# TestbedV2.net
KiCad netlist of a schematic drawn in EAGLE
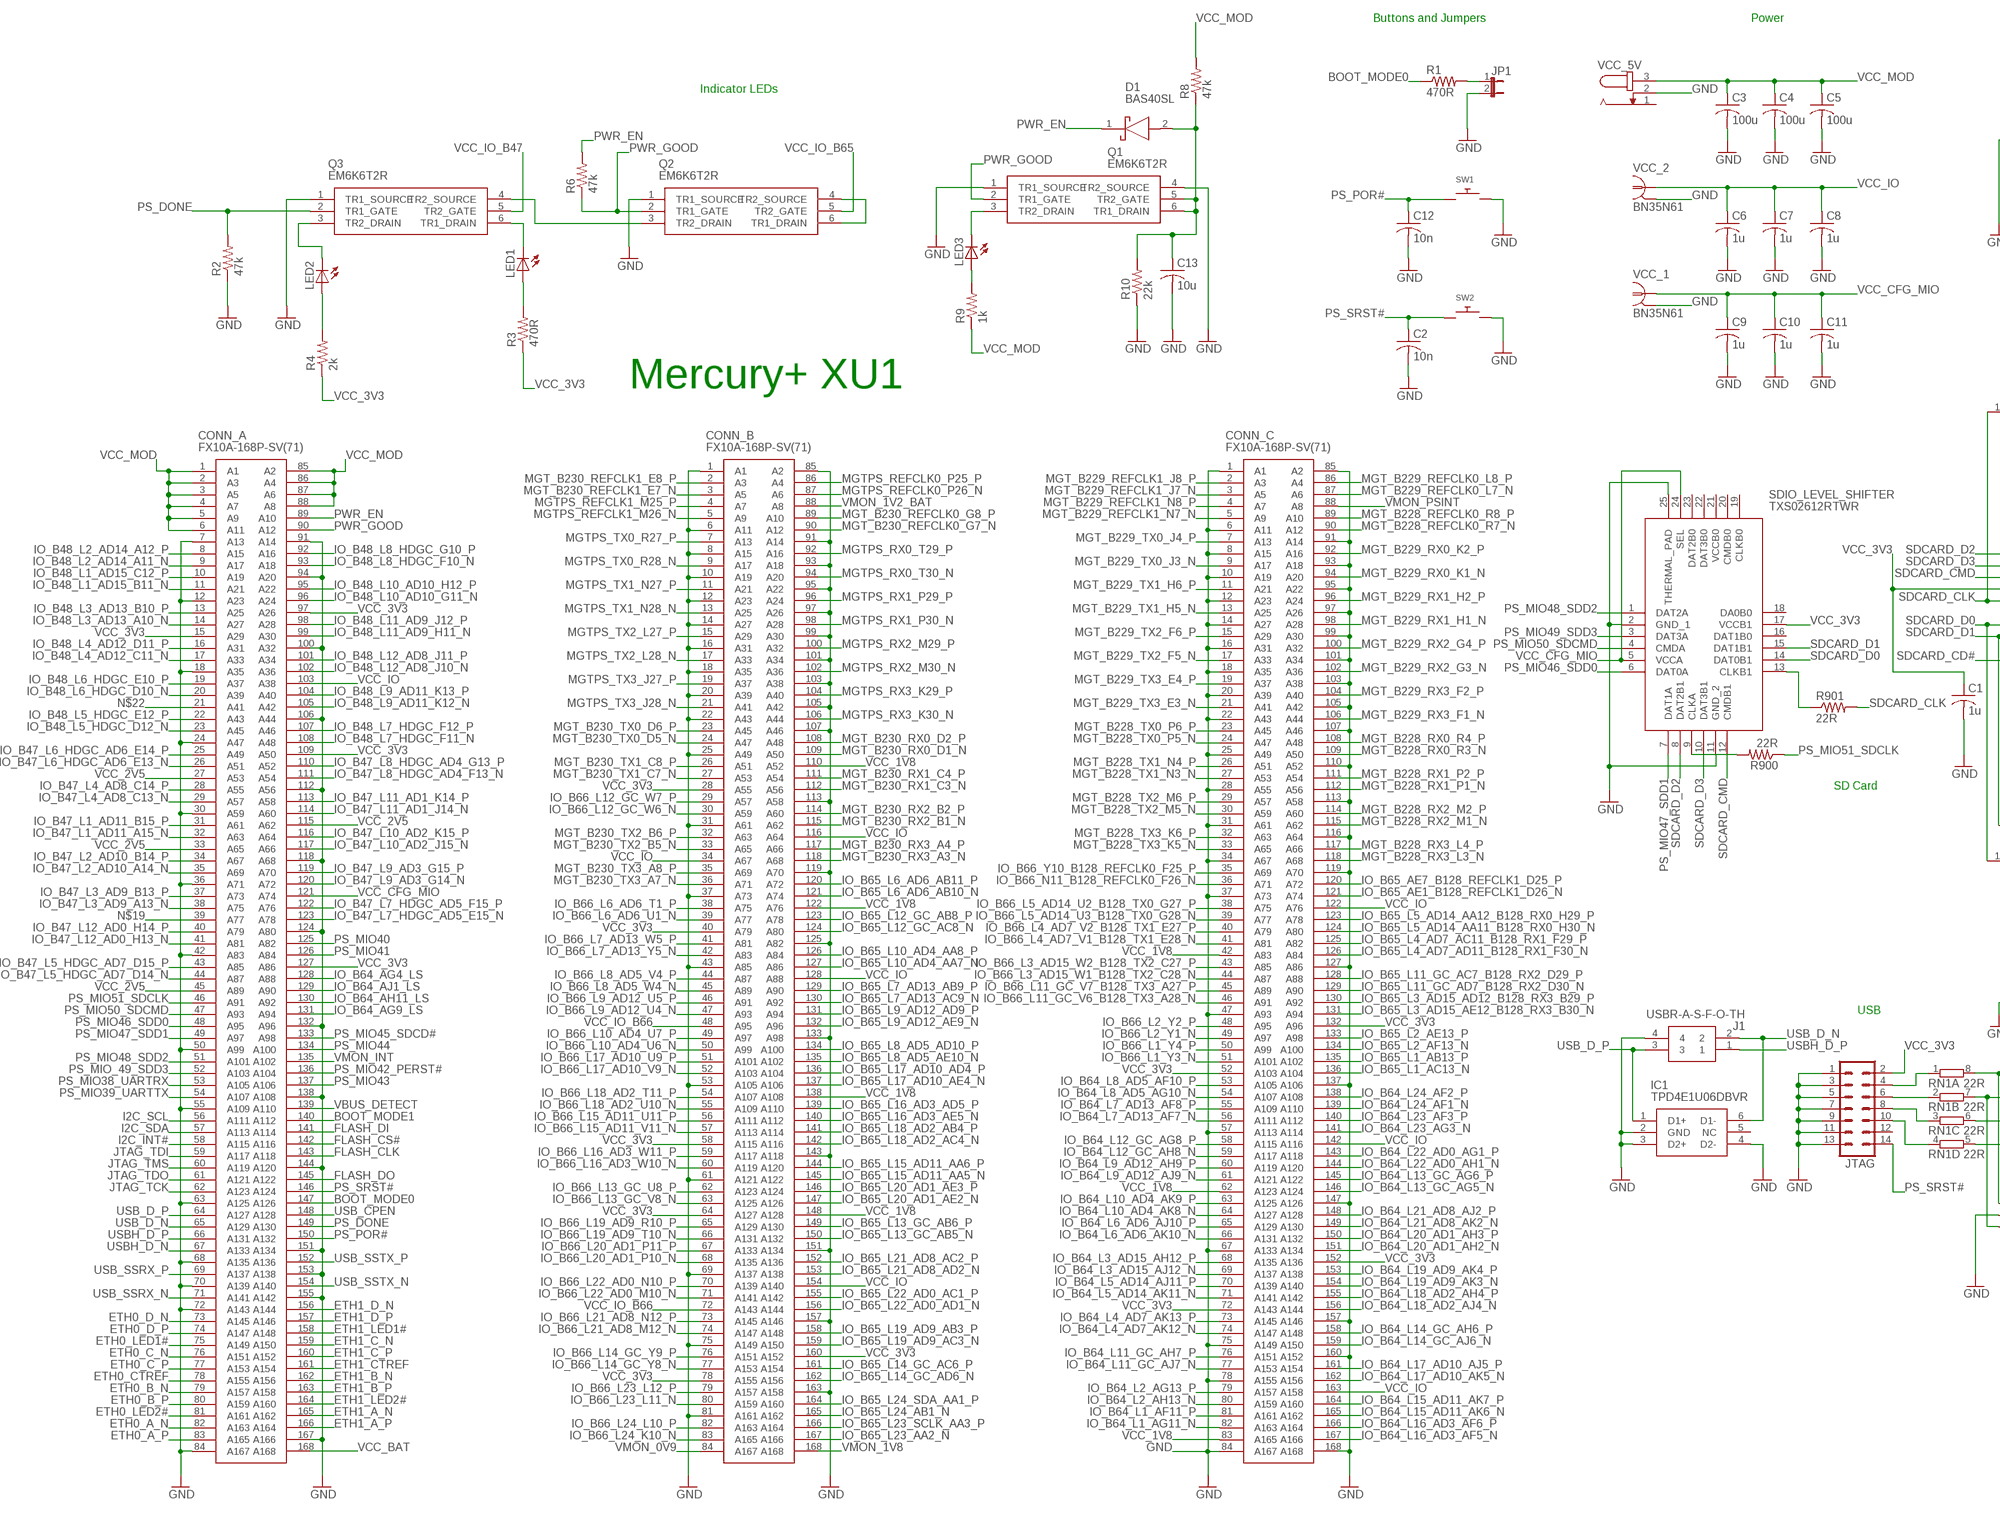
[diagram p0: schematic, sheet 1, part 1 of 2]
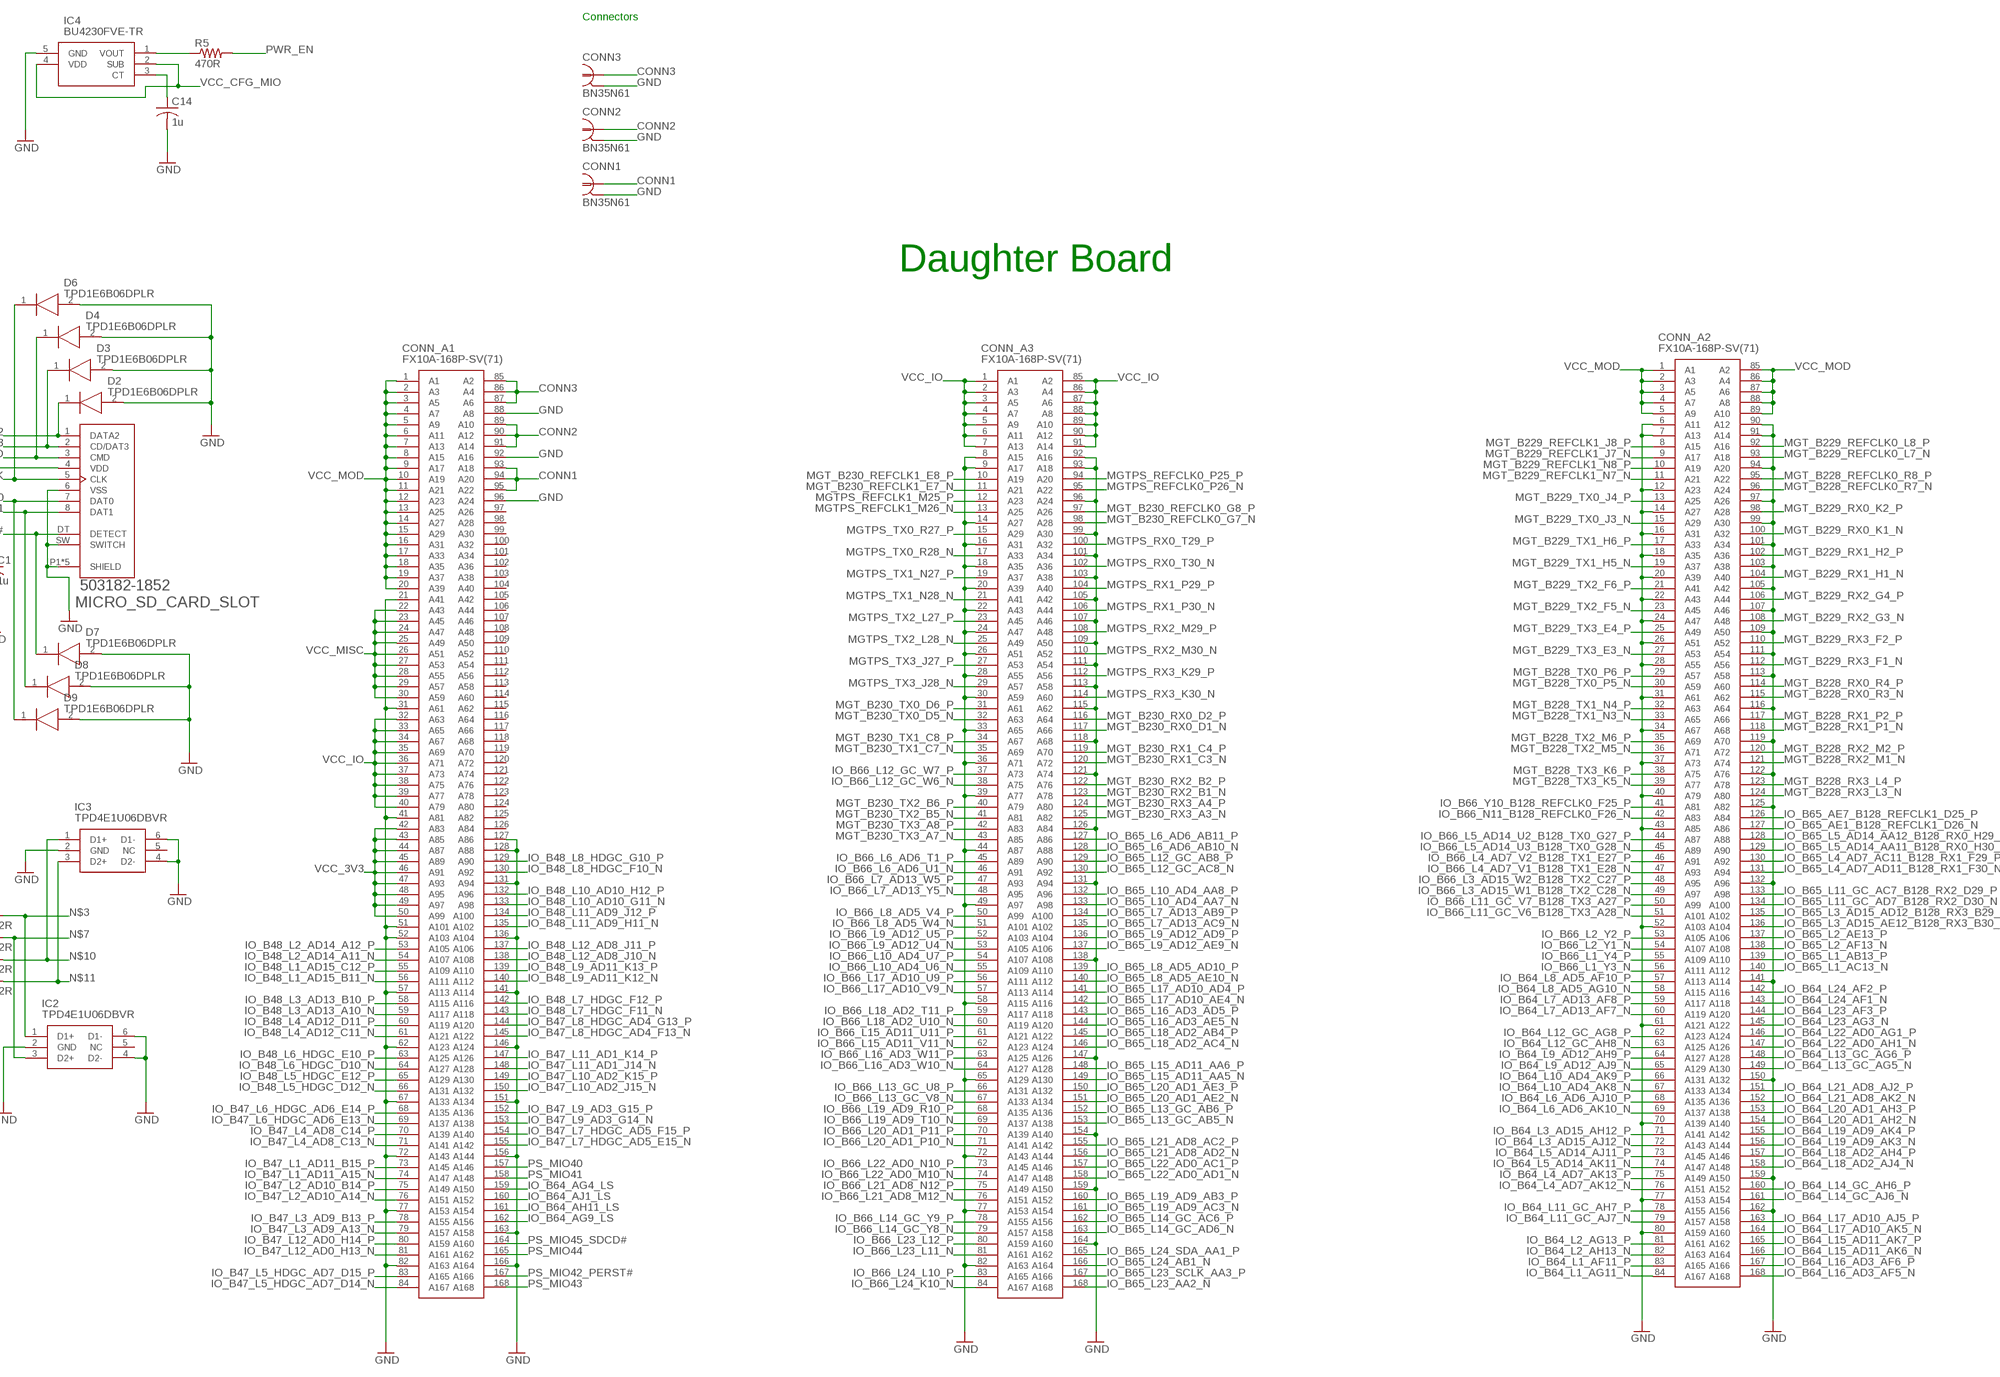
[diagram p1: schematic, sheet 1, part 2 of 2]

(export (version "E")
  (design (tool "Eeschema 10.0.6"))
  (components
    (comp (ref "C1")
      (value "1u")
      (footprint "eagle-import:C0805")
      (libsource (lib "eagle-import") (part "C-USC0805"))
    )
    (comp (ref "C2")
      (value "10n")
      (footprint "eagle-import:C0805")
      (libsource (lib "eagle-import") (part "C-USC0805"))
    )
    (comp (ref "C3")
      (value "100u")
      (footprint "eagle-import:C0805")
      (libsource (lib "eagle-import") (part "C-USC0805"))
    )
    (comp (ref "C4")
      (value "100u")
      (footprint "eagle-import:C0805")
      (libsource (lib "eagle-import") (part "C-USC0805"))
    )
    (comp (ref "C5")
      (value "100u")
      (footprint "eagle-import:C0805")
      (libsource (lib "eagle-import") (part "C-USC0805"))
    )
    (comp (ref "C6")
      (value "1u")
      (footprint "eagle-import:C0805")
      (libsource (lib "eagle-import") (part "C-USC0805"))
    )
    (comp (ref "C7")
      (value "1u")
      (footprint "eagle-import:C0805")
      (libsource (lib "eagle-import") (part "C-USC0805"))
    )
    (comp (ref "C8")
      (value "1u")
      (footprint "eagle-import:C0805")
      (libsource (lib "eagle-import") (part "C-USC0805"))
    )
    (comp (ref "C9")
      (value "1u")
      (footprint "eagle-import:C0805")
      (libsource (lib "eagle-import") (part "C-USC0805"))
    )
    (comp (ref "C10")
      (value "1u")
      (footprint "eagle-import:C0805")
      (libsource (lib "eagle-import") (part "C-USC0805"))
    )
    (comp (ref "C11")
      (value "1u")
      (footprint "eagle-import:C0805")
      (libsource (lib "eagle-import") (part "C-USC0805"))
    )
    (comp (ref "C12")
      (value "10n")
      (footprint "eagle-import:C0805")
      (libsource (lib "eagle-import") (part "C-USC0805"))
    )
    (comp (ref "C13")
      (value "10u")
      (footprint "eagle-import:C0805")
      (libsource (lib "eagle-import") (part "C-USC0805"))
    )
    (comp (ref "C14")
      (value "1u")
      (footprint "eagle-import:C0805")
      (libsource (lib "eagle-import") (part "C-USC0805"))
    )
    (comp (ref "CONN1")
      (value "BN35N61")
      (footprint "eagle-import:B35N61")
      (fields (field (name "SPICEPREFIX") "X"))
      (libsource (lib "eagle-import") (part "BN35N61"))
    )
    (comp (ref "CONN2")
      (value "BN35N61")
      (footprint "eagle-import:B35N61")
      (libsource (lib "eagle-import") (part "BN35N61"))
    )
    (comp (ref "CONN3")
      (value "BN35N61")
      (footprint "eagle-import:B35N61")
      (libsource (lib "eagle-import") (part "BN35N61"))
    )
    (comp (ref "CONN_A")
      (value "FX10A-168P-SV(71)")
      (footprint "eagle-import:FX10A-168P-SV(71)")
      (fields (field (name "MOUSER_PART_NUMBER") "798-FX10A168PSV71"))
      (libsource (lib "eagle-import") (part "FX10A-168P-SV(71)"))
    )
    (comp (ref "CONN_A1")
      (value "FX10A-168P-SV(71)")
      (footprint "eagle-import:FX10A-168P-SV(71)")
      (fields (field (name "MOUSER_PART_NUMBER") "798-FX10A168PSV71"))
      (libsource (lib "eagle-import") (part "FX10A-168P-SV(71)"))
    )
    (comp (ref "CONN_A2")
      (value "FX10A-168P-SV(71)")
      (footprint "eagle-import:FX10A-168P-SV(71)")
      (fields (field (name "MOUSER_PART_NUMBER") "798-FX10A168PSV71"))
      (libsource (lib "eagle-import") (part "FX10A-168P-SV(71)"))
    )
    (comp (ref "CONN_A3")
      (value "FX10A-168P-SV(71)")
      (footprint "eagle-import:FX10A-168P-SV(71)")
      (fields (field (name "MOUSER_PART_NUMBER") "798-FX10A168PSV71"))
      (libsource (lib "eagle-import") (part "FX10A-168P-SV(71)"))
    )
    (comp (ref "CONN_B")
      (value "FX10A-168P-SV(71)")
      (footprint "eagle-import:FX10A-168P-SV(71)")
      (fields (field (name "MOUSER_PART_NUMBER") "798-FX10A168PSV71"))
      (libsource (lib "eagle-import") (part "FX10A-168P-SV(71)"))
    )
    (comp (ref "CONN_C")
      (value "FX10A-168P-SV(71)")
      (footprint "eagle-import:FX10A-168P-SV(71)")
      (fields (field (name "MOUSER_PART_NUMBER") "798-FX10A168PSV71"))
      (libsource (lib "eagle-import") (part "FX10A-168P-SV(71)"))
    )
    (comp (ref "D1")
      (value "BAS40SL")
      (footprint "eagle-import:SODFL1006X43N")
      (fields (field (name "MOUSER_PART_NUMBER") "512-BAS40SL"))
      (libsource (lib "eagle-import") (part "BAS40SL"))
    )
    (comp (ref "D2")
      (value "TPD1E6B06DPLR")
      (footprint "eagle-import:DPL-(R-PX2SON-N2)")
      (fields (field (name "MOUSER_PART_NUMBER") "595-TPD1E6B06DPLR"))
      (libsource (lib "eagle-import") (part "TPD1E6B06DPLR"))
    )
    (comp (ref "D3")
      (value "TPD1E6B06DPLR")
      (footprint "eagle-import:DPL-(R-PX2SON-N2)")
      (fields (field (name "MOUSER_PART_NUMBER") "595-TPD1E6B06DPLR"))
      (libsource (lib "eagle-import") (part "TPD1E6B06DPLR"))
    )
    (comp (ref "D4")
      (value "TPD1E6B06DPLR")
      (footprint "eagle-import:DPL-(R-PX2SON-N2)")
      (fields (field (name "MOUSER_PART_NUMBER") "595-TPD1E6B06DPLR"))
      (libsource (lib "eagle-import") (part "TPD1E6B06DPLR"))
    )
    (comp (ref "D6")
      (value "TPD1E6B06DPLR")
      (footprint "eagle-import:DPL-(R-PX2SON-N2)")
      (fields (field (name "MOUSER_PART_NUMBER") "595-TPD1E6B06DPLR"))
      (libsource (lib "eagle-import") (part "TPD1E6B06DPLR"))
    )
    (comp (ref "D7")
      (value "TPD1E6B06DPLR")
      (footprint "eagle-import:DPL-(R-PX2SON-N2)")
      (fields (field (name "MOUSER_PART_NUMBER") "595-TPD1E6B06DPLR"))
      (libsource (lib "eagle-import") (part "TPD1E6B06DPLR"))
    )
    (comp (ref "D8")
      (value "TPD1E6B06DPLR")
      (footprint "eagle-import:DPL-(R-PX2SON-N2)")
      (fields (field (name "MOUSER_PART_NUMBER") "595-TPD1E6B06DPLR"))
      (libsource (lib "eagle-import") (part "TPD1E6B06DPLR"))
    )
    (comp (ref "D9")
      (value "TPD1E6B06DPLR")
      (footprint "eagle-import:DPL-(R-PX2SON-N2)")
      (fields (field (name "MOUSER_PART_NUMBER") "595-TPD1E6B06DPLR"))
      (libsource (lib "eagle-import") (part "TPD1E6B06DPLR"))
    )
    (comp (ref "IC1")
      (value "TPD4E1U06DBVR")
      (footprint "eagle-import:SOT95P280X145-6N")
      (fields (field (name "MOUSER_PART_NUMBER") "595-TPD4E1U06DBVR"))
      (libsource (lib "eagle-import") (part "TPD4E1U06DBVR"))
    )
    (comp (ref "IC2")
      (value "TPD4E1U06DBVR")
      (footprint "eagle-import:SOT95P280X145-6N")
      (fields (field (name "MOUSER_PART_NUMBER") "595-TPD4E1U06DBVR"))
      (libsource (lib "eagle-import") (part "TPD4E1U06DBVR"))
    )
    (comp (ref "IC3")
      (value "TPD4E1U06DBVR")
      (footprint "eagle-import:SOT95P280X145-6N")
      (fields (field (name "MOUSER_PART_NUMBER") "595-TPD4E1U06DBVR"))
      (libsource (lib "eagle-import") (part "TPD4E1U06DBVR"))
    )
    (comp (ref "IC4")
      (value "BU4230FVE-TR")
      (footprint "eagle-import:BU4230FVETR")
      (fields (field (name "MOUSER_PART_NUMBER") "755-BU4230FVE-TR"))
      (libsource (lib "eagle-import") (part "BU4230FVE-TR"))
    )
    (comp (ref "J1")
      (value "USBR-A-S-F-O-TH")
      (footprint "eagle-import:USBR-A-S-F-O-TH")
      (fields (field (name "MOUSER_PART_NUMBER") "200-USBRASFOTH"))
      (libsource (lib "eagle-import") (part "USBR-A-S-F-O-TH"))
    )
    (comp (ref "JP1")
      (value "JP1E")
      (footprint "eagle-import:JP1")
      (libsource (lib "eagle-import") (part "JP1E"))
    )
    (comp (ref "JTAG")
      (value "MA07-2")
      (footprint "eagle-import:MA07-2")
      (libsource (lib "eagle-import") (part "MA07-2"))
    )
    (comp (ref "LED1")
      (value "LEDCHIP-LED0805")
      (footprint "eagle-import:CHIP-LED0805")
      (libsource (lib "eagle-import") (part "LEDCHIP-LED0805"))
    )
    (comp (ref "LED2")
      (value "LEDCHIP-LED0805")
      (footprint "eagle-import:CHIP-LED0805")
      (libsource (lib "eagle-import") (part "LEDCHIP-LED0805"))
    )
    (comp (ref "LED3")
      (value "LEDCHIP-LED0805")
      (footprint "eagle-import:CHIP-LED0805")
      (libsource (lib "eagle-import") (part "LEDCHIP-LED0805"))
    )
    (comp (ref "MICRO_SD_CARD_SLOT")
      (value "503182-1852")
      (footprint "eagle-import:MOLEX_503182-1852")
      (fields
        (field (name "DIGI-KEY_PART_NUMBER") "WM12834CT-ND")
        (field (name "MF") "Molex")
        (field (name "MP") "5031821852")
      )
      (libsource (lib "eagle-import") (part "503182-1852"))
    )
    (comp (ref "Q1")
      (value "EM6K6T2R")
      (footprint "eagle-import:SOTFL50P160X55-6N")
      (fields (field (name "MOUSER_PART_NUMBER") "755-EM6K6T2R"))
      (libsource (lib "eagle-import") (part "EM6K6T2R"))
    )
    (comp (ref "Q2")
      (value "EM6K6T2R")
      (footprint "eagle-import:SOTFL50P160X55-6N")
      (fields (field (name "MOUSER_PART_NUMBER") "755-EM6K6T2R"))
      (libsource (lib "eagle-import") (part "EM6K6T2R"))
    )
    (comp (ref "Q3")
      (value "EM6K6T2R")
      (footprint "eagle-import:SOTFL50P160X55-6N")
      (fields (field (name "MOUSER_PART_NUMBER") "755-EM6K6T2R"))
      (libsource (lib "eagle-import") (part "EM6K6T2R"))
    )
    (comp (ref "R1")
      (value "470R")
      (footprint "eagle-import:R0805")
      (libsource (lib "eagle-import") (part "R-US_R0805"))
    )
    (comp (ref "R2")
      (value "47k")
      (footprint "eagle-import:R0805")
      (libsource (lib "eagle-import") (part "R-US_R0805"))
    )
    (comp (ref "R3")
      (value "470R")
      (footprint "eagle-import:R0805")
      (libsource (lib "eagle-import") (part "R-US_R0805"))
    )
    (comp (ref "R4")
      (value "2k")
      (footprint "eagle-import:R0805")
      (libsource (lib "eagle-import") (part "R-US_R0805"))
    )
    (comp (ref "R5")
      (value "470R")
      (footprint "eagle-import:R0805")
      (libsource (lib "eagle-import") (part "R-US_R0805"))
    )
    (comp (ref "R6")
      (value "47k")
      (footprint "eagle-import:R0805")
      (libsource (lib "eagle-import") (part "R-US_R0805"))
    )
    (comp (ref "R8")
      (value "47k")
      (footprint "eagle-import:R0805")
      (libsource (lib "eagle-import") (part "R-US_R0805"))
    )
    (comp (ref "R9")
      (value "1k")
      (footprint "eagle-import:R0805")
      (libsource (lib "eagle-import") (part "R-US_R0805"))
    )
    (comp (ref "R10")
      (value "22k")
      (footprint "eagle-import:R0805")
      (libsource (lib "eagle-import") (part "R-US_R0805"))
    )
    (comp (ref "R900")
      (value "22R")
      (footprint "eagle-import:R0805")
      (libsource (lib "eagle-import") (part "R-US_R0805"))
    )
    (comp (ref "R901")
      (value "22R")
      (footprint "eagle-import:R0805")
      (libsource (lib "eagle-import") (part "R-US_R0805"))
    )
    (comp (ref "RN1")
      (value "22R")
      (footprint "eagle-import:4X0402ARV341")
      (libsource (lib "eagle-import") (part "4R-N0402ARV341"))
    )
    (comp (ref "SDIO_LEVEL_SHIFTER")
      (value "TXS02612RTWR")
      (footprint "eagle-import:QFN50P400X400X80-25N")
      (fields (field (name "MOUSER_PART_NUMBER") "595-TXS02612RTWR"))
      (libsource (lib "eagle-import") (part "TXS02612RTWR"))
    )
    (comp (ref "SW1")
      (value "SWITCH_PUSHBUTTONSOFTTOUCHSMD_SJ")
      (footprint "eagle-import:PUSHBUTTON_SMD_SJ")
      (libsource (lib "eagle-import") (part "SWITCH_PUSHBUTTONSOFTTOUCHSMD_SJ"))
    )
    (comp (ref "SW2")
      (value "SWITCH_PUSHBUTTONSOFTTOUCHSMD_SJ")
      (footprint "eagle-import:PUSHBUTTON_SMD_SJ")
      (libsource (lib "eagle-import") (part "SWITCH_PUSHBUTTONSOFTTOUCHSMD_SJ"))
    )
    (comp (ref "VCC_1")
      (value "BN35N61")
      (footprint "eagle-import:B35N61")
      (libsource (lib "eagle-import") (part "BN35N61"))
    )
    (comp (ref "VCC_2")
      (value "BN35N61")
      (footprint "eagle-import:B35N61")
      (libsource (lib "eagle-import") (part "BN35N61"))
    )
    (comp (ref "VCC_5V")
      (value "JACK-PLUG1")
      (footprint "eagle-import:SPC4078")
      (libsource (lib "eagle-import") (part "JACK-PLUG1"))
    )
  )
  (nets
    (net (code "1") (name "/BOOT_MODE0") (class "Default")
      (node (ref "CONN_A") (pin "147") (pinfunction "A126_147") (pintype "bidirectional"))
      (node (ref "R1") (pin "1") (pinfunction "1_1") (pintype "passive"))
    )
    (net (code "2") (name "/BOOT_MODE1") (class "Default")
      (node (ref "CONN_A") (pin "140") (pinfunction "A112_140") (pintype "bidirectional"))
    )
    (net (code "3") (name "/CONN1") (class "Default")
      (node (ref "CONN1") (pin "1") (pinfunction "1_1") (pintype "passive"))
      (node (ref "CONN_A1") (pin "93") (pinfunction "A18_93") (pintype "bidirectional"))
      (node (ref "CONN_A1") (pin "94") (pinfunction "A20_94") (pintype "bidirectional"))
      (node (ref "CONN_A1") (pin "95") (pinfunction "A22_95") (pintype "bidirectional"))
    )
    (net (code "4") (name "/CONN2") (class "Default")
      (node (ref "CONN2") (pin "1") (pinfunction "1_1") (pintype "passive"))
      (node (ref "CONN_A1") (pin "89") (pinfunction "A10_89") (pintype "bidirectional"))
      (node (ref "CONN_A1") (pin "90") (pinfunction "A12_90") (pintype "bidirectional"))
      (node (ref "CONN_A1") (pin "91") (pinfunction "A14_91") (pintype "bidirectional"))
    )
    (net (code "5") (name "/CONN3") (class "Default")
      (node (ref "CONN3") (pin "1") (pinfunction "1_1") (pintype "passive"))
      (node (ref "CONN_A1") (pin "85") (pinfunction "A2_85") (pintype "bidirectional"))
      (node (ref "CONN_A1") (pin "86") (pinfunction "A4_86") (pintype "bidirectional"))
      (node (ref "CONN_A1") (pin "87") (pinfunction "A6_87") (pintype "bidirectional"))
    )
    (net (code "6") (name "/ETH0_A_N") (class "Default")
      (node (ref "CONN_A") (pin "82") (pinfunction "A163_82") (pintype "bidirectional"))
    )
    (net (code "7") (name "/ETH0_A_P") (class "Default")
      (node (ref "CONN_A") (pin "83") (pinfunction "A165_83") (pintype "bidirectional"))
    )
    (net (code "8") (name "/ETH0_B_N") (class "Default")
      (node (ref "CONN_A") (pin "79") (pinfunction "A157_79") (pintype "bidirectional"))
    )
    (net (code "9") (name "/ETH0_B_P") (class "Default")
      (node (ref "CONN_A") (pin "80") (pinfunction "A159_80") (pintype "bidirectional"))
    )
    (net (code "10") (name "/ETH0_CTREF") (class "Default")
      (node (ref "CONN_A") (pin "78") (pinfunction "A155_78") (pintype "bidirectional"))
    )
    (net (code "11") (name "/ETH0_C_N") (class "Default")
      (node (ref "CONN_A") (pin "76") (pinfunction "A151_76") (pintype "bidirectional"))
    )
    (net (code "12") (name "/ETH0_C_P") (class "Default")
      (node (ref "CONN_A") (pin "77") (pinfunction "A153_77") (pintype "bidirectional"))
    )
    (net (code "13") (name "/ETH0_D_N") (class "Default")
      (node (ref "CONN_A") (pin "73") (pinfunction "A145_73") (pintype "bidirectional"))
    )
    (net (code "14") (name "/ETH0_D_P") (class "Default")
      (node (ref "CONN_A") (pin "74") (pinfunction "A147_74") (pintype "bidirectional"))
    )
    (net (code "15") (name "/ETH0_LED1#") (class "Default")
      (node (ref "CONN_A") (pin "75") (pinfunction "A149_75") (pintype "bidirectional"))
    )
    (net (code "16") (name "/ETH0_LED2#") (class "Default")
      (node (ref "CONN_A") (pin "81") (pinfunction "A161_81") (pintype "bidirectional"))
    )
    (net (code "17") (name "/ETH1_A_N") (class "Default")
      (node (ref "CONN_A") (pin "165") (pinfunction "A162_165") (pintype "bidirectional"))
    )
    (net (code "18") (name "/ETH1_A_P") (class "Default")
      (node (ref "CONN_A") (pin "166") (pinfunction "A164_166") (pintype "bidirectional"))
    )
    (net (code "19") (name "/ETH1_B_N") (class "Default")
      (node (ref "CONN_A") (pin "162") (pinfunction "A156_162") (pintype "bidirectional"))
    )
    (net (code "20") (name "/ETH1_B_P") (class "Default")
      (node (ref "CONN_A") (pin "163") (pinfunction "A158_163") (pintype "bidirectional"))
    )
    (net (code "21") (name "/ETH1_CTREF") (class "Default")
      (node (ref "CONN_A") (pin "161") (pinfunction "A154_161") (pintype "bidirectional"))
    )
    (net (code "22") (name "/ETH1_C_N") (class "Default")
      (node (ref "CONN_A") (pin "159") (pinfunction "A150_159") (pintype "bidirectional"))
    )
    (net (code "23") (name "/ETH1_C_P") (class "Default")
      (node (ref "CONN_A") (pin "160") (pinfunction "A152_160") (pintype "bidirectional"))
    )
    (net (code "24") (name "/ETH1_D_N") (class "Default")
      (node (ref "CONN_A") (pin "156") (pinfunction "A144_156") (pintype "bidirectional"))
    )
    (net (code "25") (name "/ETH1_D_P") (class "Default")
      (node (ref "CONN_A") (pin "157") (pinfunction "A146_157") (pintype "bidirectional"))
    )
    (net (code "26") (name "/ETH1_LED1#") (class "Default")
      (node (ref "CONN_A") (pin "158") (pinfunction "A148_158") (pintype "bidirectional"))
    )
    (net (code "27") (name "/ETH1_LED2#") (class "Default")
      (node (ref "CONN_A") (pin "164") (pinfunction "A160_164") (pintype "bidirectional"))
    )
    (net (code "28") (name "/FLASH_CLK") (class "Default")
      (node (ref "CONN_A") (pin "143") (pinfunction "A118_143") (pintype "bidirectional"))
    )
    (net (code "29") (name "/FLASH_CS#") (class "Default")
      (node (ref "CONN_A") (pin "142") (pinfunction "A116_142") (pintype "bidirectional"))
    )
    (net (code "30") (name "/FLASH_DI") (class "Default")
      (node (ref "CONN_A") (pin "141") (pinfunction "A114_141") (pintype "bidirectional"))
    )
    (net (code "31") (name "/FLASH_DO") (class "Default")
      (node (ref "CONN_A") (pin "145") (pinfunction "A122_145") (pintype "bidirectional"))
    )
    (net (code "32") (name "/I2C_INT#") (class "Default")
      (node (ref "CONN_A") (pin "58") (pinfunction "A115_58") (pintype "bidirectional"))
    )
    (net (code "33") (name "/I2C_SCL") (class "Default")
      (node (ref "CONN_A") (pin "56") (pinfunction "A111_56") (pintype "bidirectional"))
    )
    (net (code "34") (name "/I2C_SDA") (class "Default")
      (node (ref "CONN_A") (pin "57") (pinfunction "A113_57") (pintype "bidirectional"))
    )
    (net (code "35") (name "/IO_B47_L1_AD11_A15_N") (class "Default")
      (node (ref "CONN_A") (pin "32") (pinfunction "A63_32") (pintype "bidirectional"))
      (node (ref "CONN_A1") (pin "74") (pinfunction "A147_74") (pintype "bidirectional"))
    )
    (net (code "36") (name "/IO_B47_L1_AD11_B15_P") (class "Default")
      (node (ref "CONN_A") (pin "31") (pinfunction "A61_31") (pintype "bidirectional"))
      (node (ref "CONN_A1") (pin "73") (pinfunction "A145_73") (pintype "bidirectional"))
    )
    (net (code "37") (name "/IO_B47_L2_AD10_A14_N") (class "Default")
      (node (ref "CONN_A") (pin "35") (pinfunction "A69_35") (pintype "bidirectional"))
      (node (ref "CONN_A1") (pin "76") (pinfunction "A151_76") (pintype "bidirectional"))
    )
    (net (code "38") (name "/IO_B47_L2_AD10_B14_P") (class "Default")
      (node (ref "CONN_A") (pin "34") (pinfunction "A67_34") (pintype "bidirectional"))
      (node (ref "CONN_A1") (pin "75") (pinfunction "A149_75") (pintype "bidirectional"))
    )
    (net (code "39") (name "/IO_B47_L3_AD9_A13_N") (class "Default")
      (node (ref "CONN_A") (pin "38") (pinfunction "A75_38") (pintype "bidirectional"))
      (node (ref "CONN_A1") (pin "79") (pinfunction "A157_79") (pintype "bidirectional"))
    )
    (net (code "40") (name "/IO_B47_L3_AD9_B13_P") (class "Default")
      (node (ref "CONN_A") (pin "37") (pinfunction "A73_37") (pintype "bidirectional"))
      (node (ref "CONN_A1") (pin "78") (pinfunction "A155_78") (pintype "bidirectional"))
    )
    (net (code "41") (name "/IO_B47_L4_AD8_C13_N") (class "Default")
      (node (ref "CONN_A") (pin "29") (pinfunction "A57_29") (pintype "bidirectional"))
      (node (ref "CONN_A1") (pin "71") (pinfunction "A141_71") (pintype "bidirectional"))
    )
    (net (code "42") (name "/IO_B47_L4_AD8_C14_P") (class "Default")
      (node (ref "CONN_A") (pin "28") (pinfunction "A55_28") (pintype "bidirectional"))
      (node (ref "CONN_A1") (pin "70") (pinfunction "A139_70") (pintype "bidirectional"))
    )
    (net (code "43") (name "/IO_B47_L5_HDGC_AD7_D14_N") (class "Default")
      (node (ref "CONN_A") (pin "44") (pinfunction "A87_44") (pintype "bidirectional"))
      (node (ref "CONN_A1") (pin "84") (pinfunction "A167_84") (pintype "bidirectional"))
    )
    (net (code "44") (name "/IO_B47_L5_HDGC_AD7_D15_P") (class "Default")
      (node (ref "CONN_A") (pin "43") (pinfunction "A85_43") (pintype "bidirectional"))
      (node (ref "CONN_A1") (pin "83") (pinfunction "A165_83") (pintype "bidirectional"))
    )
    (net (code "45") (name "/IO_B47_L6_HDGC_AD6_E13_N") (class "Default")
      (node (ref "CONN_A") (pin "26") (pinfunction "A51_26") (pintype "bidirectional"))
      (node (ref "CONN_A1") (pin "69") (pinfunction "A137_69") (pintype "bidirectional"))
    )
    (net (code "46") (name "/IO_B47_L6_HDGC_AD6_E14_P") (class "Default")
      (node (ref "CONN_A") (pin "25") (pinfunction "A49_25") (pintype "bidirectional"))
      (node (ref "CONN_A1") (pin "68") (pinfunction "A135_68") (pintype "bidirectional"))
    )
    (net (code "47") (name "/IO_B47_L7_HDGC_AD5_E15_N") (class "Default")
      (node (ref "CONN_A") (pin "123") (pinfunction "A78_123") (pintype "bidirectional"))
      (node (ref "CONN_A1") (pin "155") (pinfunction "A142_155") (pintype "bidirectional"))
    )
    (net (code "48") (name "/IO_B47_L7_HDGC_AD5_F15_P") (class "Default")
      (node (ref "CONN_A") (pin "122") (pinfunction "A76_122") (pintype "bidirectional"))
      (node (ref "CONN_A1") (pin "154") (pinfunction "A140_154") (pintype "bidirectional"))
    )
    (net (code "49") (name "/IO_B47_L8_HDGC_AD4_F13_N") (class "Default")
      (node (ref "CONN_A") (pin "111") (pinfunction "A54_111") (pintype "bidirectional"))
      (node (ref "CONN_A1") (pin "145") (pinfunction "A122_145") (pintype "bidirectional"))
    )
    (net (code "50") (name "/IO_B47_L8_HDGC_AD4_G13_P") (class "Default")
      (node (ref "CONN_A") (pin "110") (pinfunction "A52_110") (pintype "bidirectional"))
      (node (ref "CONN_A1") (pin "144") (pinfunction "A120_144") (pintype "bidirectional"))
    )
    (net (code "51") (name "/IO_B47_L9_AD3_G14_N") (class "Default")
      (node (ref "CONN_A") (pin "120") (pinfunction "A72_120") (pintype "bidirectional"))
      (node (ref "CONN_A1") (pin "153") (pinfunction "A138_153") (pintype "bidirectional"))
    )
    (net (code "52") (name "/IO_B47_L9_AD3_G15_P") (class "Default")
      (node (ref "CONN_A") (pin "119") (pinfunction "A70_119") (pintype "bidirectional"))
      (node (ref "CONN_A1") (pin "152") (pinfunction "A136_152") (pintype "bidirectional"))
    )
    (net (code "53") (name "/IO_B47_L10_AD2_J15_N") (class "Default")
      (node (ref "CONN_A") (pin "117") (pinfunction "A66_117") (pintype "bidirectional"))
      (node (ref "CONN_A1") (pin "150") (pinfunction "A132_150") (pintype "bidirectional"))
    )
    (net (code "54") (name "/IO_B47_L10_AD2_K15_P") (class "Default")
      (node (ref "CONN_A") (pin "116") (pinfunction "A64_116") (pintype "bidirectional"))
      (node (ref "CONN_A1") (pin "149") (pinfunction "A130_149") (pintype "bidirectional"))
    )
    (net (code "55") (name "/IO_B47_L11_AD1_J14_N") (class "Default")
      (node (ref "CONN_A") (pin "114") (pinfunction "A60_114") (pintype "bidirectional"))
      (node (ref "CONN_A1") (pin "148") (pinfunction "A128_148") (pintype "bidirectional"))
    )
    (net (code "56") (name "/IO_B47_L11_AD1_K14_P") (class "Default")
      (node (ref "CONN_A") (pin "113") (pinfunction "A58_113") (pintype "bidirectional"))
      (node (ref "CONN_A1") (pin "147") (pinfunction "A126_147") (pintype "bidirectional"))
    )
    (net (code "57") (name "/IO_B47_L12_AD0_H13_N") (class "Default")
      (node (ref "CONN_A") (pin "41") (pinfunction "A81_41") (pintype "bidirectional"))
      (node (ref "CONN_A1") (pin "81") (pinfunction "A161_81") (pintype "bidirectional"))
    )
    (net (code "58") (name "/IO_B47_L12_AD0_H14_P") (class "Default")
      (node (ref "CONN_A") (pin "40") (pinfunction "A79_40") (pintype "bidirectional"))
      (node (ref "CONN_A1") (pin "80") (pinfunction "A159_80") (pintype "bidirectional"))
    )
    (net (code "59") (name "/IO_B48_L1_AD15_B11_N") (class "Default")
      (node (ref "CONN_A") (pin "11") (pinfunction "A21_11") (pintype "bidirectional"))
      (node (ref "CONN_A1") (pin "56") (pinfunction "A111_56") (pintype "bidirectional"))
    )
    (net (code "60") (name "/IO_B48_L1_AD15_C12_P") (class "Default")
      (node (ref "CONN_A") (pin "10") (pinfunction "A19_10") (pintype "bidirectional"))
      (node (ref "CONN_A1") (pin "55") (pinfunction "A109_55") (pintype "bidirectional"))
    )
    (net (code "61") (name "/IO_B48_L2_AD14_A11_N") (class "Default")
      (node (ref "CONN_A") (pin "9") (pinfunction "A17_9") (pintype "bidirectional"))
      (node (ref "CONN_A1") (pin "54") (pinfunction "A107_54") (pintype "bidirectional"))
    )
    (net (code "62") (name "/IO_B48_L2_AD14_A12_P") (class "Default")
      (node (ref "CONN_A") (pin "8") (pinfunction "A15_8") (pintype "bidirectional"))
      (node (ref "CONN_A1") (pin "53") (pinfunction "A105_53") (pintype "bidirectional"))
    )
    (net (code "63") (name "/IO_B48_L3_AD13_A10_N") (class "Default")
      (node (ref "CONN_A") (pin "14") (pinfunction "A27_14") (pintype "bidirectional"))
      (node (ref "CONN_A1") (pin "59") (pinfunction "A117_59") (pintype "bidirectional"))
    )
    (net (code "64") (name "/IO_B48_L3_AD13_B10_P") (class "Default")
      (node (ref "CONN_A") (pin "13") (pinfunction "A25_13") (pintype "bidirectional"))
      (node (ref "CONN_A1") (pin "58") (pinfunction "A115_58") (pintype "bidirectional"))
    )
    (net (code "65") (name "/IO_B48_L4_AD12_C11_N") (class "Default")
      (node (ref "CONN_A") (pin "17") (pinfunction "A33_17") (pintype "bidirectional"))
      (node (ref "CONN_A1") (pin "61") (pinfunction "A121_61") (pintype "bidirectional"))
    )
    (net (code "66") (name "/IO_B48_L4_AD12_D11_P") (class "Default")
      (node (ref "CONN_A") (pin "16") (pinfunction "A31_16") (pintype "bidirectional"))
      (node (ref "CONN_A1") (pin "60") (pinfunction "A119_60") (pintype "bidirectional"))
    )
    (net (code "67") (name "/IO_B48_L5_HDGC_D12_N") (class "Default")
      (node (ref "CONN_A") (pin "23") (pinfunction "A45_23") (pintype "bidirectional"))
      (node (ref "CONN_A1") (pin "66") (pinfunction "A131_66") (pintype "bidirectional"))
    )
    (net (code "68") (name "/IO_B48_L5_HDGC_E12_P") (class "Default")
      (node (ref "CONN_A") (pin "22") (pinfunction "A43_22") (pintype "bidirectional"))
      (node (ref "CONN_A1") (pin "65") (pinfunction "A129_65") (pintype "bidirectional"))
    )
    (net (code "69") (name "/IO_B48_L6_HDGC_D10_N") (class "Default")
      (node (ref "CONN_A") (pin "20") (pinfunction "A39_20") (pintype "bidirectional"))
      (node (ref "CONN_A1") (pin "64") (pinfunction "A127_64") (pintype "bidirectional"))
    )
    (net (code "70") (name "/IO_B48_L6_HDGC_E10_P") (class "Default")
      (node (ref "CONN_A") (pin "19") (pinfunction "A37_19") (pintype "bidirectional"))
      (node (ref "CONN_A1") (pin "63") (pinfunction "A125_63") (pintype "bidirectional"))
    )
    (net (code "71") (name "/IO_B48_L7_HDGC_F11_N") (class "Default")
      (node (ref "CONN_A") (pin "108") (pinfunction "A48_108") (pintype "bidirectional"))
      (node (ref "CONN_A1") (pin "143") (pinfunction "A118_143") (pintype "bidirectional"))
    )
    (net (code "72") (name "/IO_B48_L7_HDGC_F12_P") (class "Default")
      (node (ref "CONN_A") (pin "107") (pinfunction "A46_107") (pintype "bidirectional"))
      (node (ref "CONN_A1") (pin "142") (pinfunction "A116_142") (pintype "bidirectional"))
    )
    (net (code "73") (name "/IO_B48_L8_HDGC_F10_N") (class "Default")
      (node (ref "CONN_A") (pin "93") (pinfunction "A18_93") (pintype "bidirectional"))
      (node (ref "CONN_A1") (pin "130") (pinfunction "A92_130") (pintype "bidirectional"))
    )
    (net (code "74") (name "/IO_B48_L8_HDGC_G10_P") (class "Default")
      (node (ref "CONN_A") (pin "92") (pinfunction "A16_92") (pintype "bidirectional"))
      (node (ref "CONN_A1") (pin "129") (pinfunction "A90_129") (pintype "bidirectional"))
    )
    (net (code "75") (name "/IO_B48_L9_AD11_K12_N") (class "Default")
      (node (ref "CONN_A") (pin "105") (pinfunction "A42_105") (pintype "bidirectional"))
      (node (ref "CONN_A1") (pin "140") (pinfunction "A112_140") (pintype "bidirectional"))
    )
    (net (code "76") (name "/IO_B48_L9_AD11_K13_P") (class "Default")
      (node (ref "CONN_A") (pin "104") (pinfunction "A40_104") (pintype "bidirectional"))
      (node (ref "CONN_A1") (pin "139") (pinfunction "A110_139") (pintype "bidirectional"))
    )
    (net (code "77") (name "/IO_B48_L10_AD10_G11_N") (class "Default")
      (node (ref "CONN_A") (pin "96") (pinfunction "A24_96") (pintype "bidirectional"))
      (node (ref "CONN_A1") (pin "133") (pinfunction "A98_133") (pintype "bidirectional"))
    )
    (net (code "78") (name "/IO_B48_L10_AD10_H12_P") (class "Default")
      (node (ref "CONN_A") (pin "95") (pinfunction "A22_95") (pintype "bidirectional"))
      (node (ref "CONN_A1") (pin "132") (pinfunction "A96_132") (pintype "bidirectional"))
    )
    (net (code "79") (name "/IO_B48_L11_AD9_H11_N") (class "Default")
      (node (ref "CONN_A") (pin "99") (pinfunction "A30_99") (pintype "bidirectional"))
      (node (ref "CONN_A1") (pin "135") (pinfunction "A102_135") (pintype "bidirectional"))
    )
    (net (code "80") (name "/IO_B48_L11_AD9_J12_P") (class "Default")
      (node (ref "CONN_A") (pin "98") (pinfunction "A28_98") (pintype "bidirectional"))
      (node (ref "CONN_A1") (pin "134") (pinfunction "A100_134") (pintype "bidirectional"))
    )
    (net (code "81") (name "/IO_B48_L12_AD8_J10_N") (class "Default")
      (node (ref "CONN_A") (pin "102") (pinfunction "A36_102") (pintype "bidirectional"))
      (node (ref "CONN_A1") (pin "138") (pinfunction "A108_138") (pintype "bidirectional"))
    )
    (net (code "82") (name "/IO_B48_L12_AD8_J11_P") (class "Default")
      (node (ref "CONN_A") (pin "101") (pinfunction "A34_101") (pintype "bidirectional"))
      (node (ref "CONN_A1") (pin "137") (pinfunction "A106_137") (pintype "bidirectional"))
    )
    (net (code "83") (name "/IO_B64_AG4_LS") (class "Default")
      (node (ref "CONN_A") (pin "128") (pinfunction "A88_128") (pintype "bidirectional"))
      (node (ref "CONN_A1") (pin "159") (pinfunction "A150_159") (pintype "bidirectional"))
    )
    (net (code "84") (name "/IO_B64_AG9_LS") (class "Default")
      (node (ref "CONN_A") (pin "131") (pinfunction "A94_131") (pintype "bidirectional"))
      (node (ref "CONN_A1") (pin "162") (pinfunction "A156_162") (pintype "bidirectional"))
    )
    (net (code "85") (name "/IO_B64_AH11_LS") (class "Default")
      (node (ref "CONN_A") (pin "130") (pinfunction "A92_130") (pintype "bidirectional"))
      (node (ref "CONN_A1") (pin "161") (pinfunction "A154_161") (pintype "bidirectional"))
    )
    (net (code "86") (name "/IO_B64_AJ1_LS") (class "Default")
      (node (ref "CONN_A") (pin "129") (pinfunction "A90_129") (pintype "bidirectional"))
      (node (ref "CONN_A1") (pin "160") (pinfunction "A152_160") (pintype "bidirectional"))
    )
    (net (code "87") (name "/IO_B64_L1_AF11_P") (class "Default")
      (node (ref "CONN_A2") (pin "83") (pinfunction "A165_83") (pintype "bidirectional"))
      (node (ref "CONN_C") (pin "81") (pinfunction "A161_81") (pintype "bidirectional"))
    )
    (net (code "88") (name "/IO_B64_L1_AG11_N") (class "Default")
      (node (ref "CONN_A2") (pin "84") (pinfunction "A167_84") (pintype "bidirectional"))
      (node (ref "CONN_C") (pin "82") (pinfunction "A163_82") (pintype "bidirectional"))
    )
    (net (code "89") (name "/IO_B64_L2_AG13_P") (class "Default")
      (node (ref "CONN_A2") (pin "81") (pinfunction "A161_81") (pintype "bidirectional"))
      (node (ref "CONN_C") (pin "79") (pinfunction "A157_79") (pintype "bidirectional"))
    )
    (net (code "90") (name "/IO_B64_L2_AH13_N") (class "Default")
      (node (ref "CONN_A2") (pin "82") (pinfunction "A163_82") (pintype "bidirectional"))
      (node (ref "CONN_C") (pin "80") (pinfunction "A159_80") (pintype "bidirectional"))
    )
    (net (code "91") (name "/IO_B64_L3_AD15_AH12_P") (class "Default")
      (node (ref "CONN_A2") (pin "71") (pinfunction "A141_71") (pintype "bidirectional"))
      (node (ref "CONN_C") (pin "68") (pinfunction "A135_68") (pintype "bidirectional"))
    )
    (net (code "92") (name "/IO_B64_L3_AD15_AJ12_N") (class "Default")
      (node (ref "CONN_A2") (pin "72") (pinfunction "A143_72") (pintype "bidirectional"))
      (node (ref "CONN_C") (pin "69") (pinfunction "A137_69") (pintype "bidirectional"))
    )
    (net (code "93") (name "/IO_B64_L4_AD7_AK12_N") (class "Default")
      (node (ref "CONN_A2") (pin "76") (pinfunction "A151_76") (pintype "bidirectional"))
      (node (ref "CONN_C") (pin "74") (pinfunction "A147_74") (pintype "bidirectional"))
    )
    (net (code "94") (name "/IO_B64_L4_AD7_AK13_P") (class "Default")
      (node (ref "CONN_A2") (pin "75") (pinfunction "A149_75") (pintype "bidirectional"))
      (node (ref "CONN_C") (pin "73") (pinfunction "A145_73") (pintype "bidirectional"))
    )
    (net (code "95") (name "/IO_B64_L5_AD14_AJ11_P") (class "Default")
      (node (ref "CONN_A2") (pin "73") (pinfunction "A145_73") (pintype "bidirectional"))
      (node (ref "CONN_C") (pin "70") (pinfunction "A139_70") (pintype "bidirectional"))
    )
    (net (code "96") (name "/IO_B64_L5_AD14_AK11_N") (class "Default")
      (node (ref "CONN_A2") (pin "74") (pinfunction "A147_74") (pintype "bidirectional"))
      (node (ref "CONN_C") (pin "71") (pinfunction "A141_71") (pintype "bidirectional"))
    )
    (net (code "97") (name "/IO_B64_L6_AD6_AJ10_P") (class "Default")
      (node (ref "CONN_A2") (pin "68") (pinfunction "A135_68") (pintype "bidirectional"))
      (node (ref "CONN_C") (pin "65") (pinfunction "A129_65") (pintype "bidirectional"))
    )
    (net (code "98") (name "/IO_B64_L6_AD6_AK10_N") (class "Default")
      (node (ref "CONN_A2") (pin "69") (pinfunction "A137_69") (pintype "bidirectional"))
      (node (ref "CONN_C") (pin "66") (pinfunction "A131_66") (pintype "bidirectional"))
    )
    (net (code "99") (name "/IO_B64_L7_AD13_AF7_N") (class "Default")
      (node (ref "CONN_A2") (pin "60") (pinfunction "A119_60") (pintype "bidirectional"))
      (node (ref "CONN_C") (pin "56") (pinfunction "A111_56") (pintype "bidirectional"))
    )
    (net (code "100") (name "/IO_B64_L7_AD13_AF8_P") (class "Default")
      (node (ref "CONN_A2") (pin "59") (pinfunction "A117_59") (pintype "bidirectional"))
      (node (ref "CONN_C") (pin "55") (pinfunction "A109_55") (pintype "bidirectional"))
    )
    (net (code "101") (name "/IO_B64_L8_AD5_AF10_P") (class "Default")
      (node (ref "CONN_A2") (pin "57") (pinfunction "A113_57") (pintype "bidirectional"))
      (node (ref "CONN_C") (pin "53") (pinfunction "A105_53") (pintype "bidirectional"))
    )
    (net (code "102") (name "/IO_B64_L8_AD5_AG10_N") (class "Default")
      (node (ref "CONN_A2") (pin "58") (pinfunction "A115_58") (pintype "bidirectional"))
      (node (ref "CONN_C") (pin "54") (pinfunction "A107_54") (pintype "bidirectional"))
    )
    (net (code "103") (name "/IO_B64_L9_AD12_AH9_P") (class "Default")
      (node (ref "CONN_A2") (pin "64") (pinfunction "A127_64") (pintype "bidirectional"))
      (node (ref "CONN_C") (pin "60") (pinfunction "A119_60") (pintype "bidirectional"))
    )
    (net (code "104") (name "/IO_B64_L9_AD12_AJ9_N") (class "Default")
      (node (ref "CONN_A2") (pin "65") (pinfunction "A129_65") (pintype "bidirectional"))
      (node (ref "CONN_C") (pin "61") (pinfunction "A121_61") (pintype "bidirectional"))
    )
    (net (code "105") (name "/IO_B64_L10_AD4_AK8_N") (class "Default")
      (node (ref "CONN_A2") (pin "67") (pinfunction "A133_67") (pintype "bidirectional"))
      (node (ref "CONN_C") (pin "64") (pinfunction "A127_64") (pintype "bidirectional"))
    )
    (net (code "106") (name "/IO_B64_L10_AD4_AK9_P") (class "Default")
      (node (ref "CONN_A2") (pin "66") (pinfunction "A131_66") (pintype "bidirectional"))
      (node (ref "CONN_C") (pin "63") (pinfunction "A125_63") (pintype "bidirectional"))
    )
    (net (code "107") (name "/IO_B64_L11_GC_AH7_P") (class "Default")
      (node (ref "CONN_A2") (pin "78") (pinfunction "A155_78") (pintype "bidirectional"))
      (node (ref "CONN_C") (pin "76") (pinfunction "A151_76") (pintype "bidirectional"))
    )
    (net (code "108") (name "/IO_B64_L11_GC_AJ7_N") (class "Default")
      (node (ref "CONN_A2") (pin "79") (pinfunction "A157_79") (pintype "bidirectional"))
      (node (ref "CONN_C") (pin "77") (pinfunction "A153_77") (pintype "bidirectional"))
    )
    (net (code "109") (name "/IO_B64_L12_GC_AG8_P") (class "Default")
      (node (ref "CONN_A2") (pin "62") (pinfunction "A123_62") (pintype "bidirectional"))
      (node (ref "CONN_C") (pin "58") (pinfunction "A115_58") (pintype "bidirectional"))
    )
    (net (code "110") (name "/IO_B64_L12_GC_AH8_N") (class "Default")
      (node (ref "CONN_A2") (pin "63") (pinfunction "A125_63") (pintype "bidirectional"))
      (node (ref "CONN_C") (pin "59") (pinfunction "A117_59") (pintype "bidirectional"))
    )
    (net (code "111") (name "/IO_B64_L13_GC_AG5_N") (class "Default")
      (node (ref "CONN_A2") (pin "149") (pinfunction "A130_149") (pintype "bidirectional"))
      (node (ref "CONN_C") (pin "146") (pinfunction "A124_146") (pintype "bidirectional"))
    )
    (net (code "112") (name "/IO_B64_L13_GC_AG6_P") (class "Default")
      (node (ref "CONN_A2") (pin "148") (pinfunction "A128_148") (pintype "bidirectional"))
      (node (ref "CONN_C") (pin "145") (pinfunction "A122_145") (pintype "bidirectional"))
    )
    (net (code "113") (name "/IO_B64_L14_GC_AH6_P") (class "Default")
      (node (ref "CONN_A2") (pin "160") (pinfunction "A152_160") (pintype "bidirectional"))
      (node (ref "CONN_C") (pin "158") (pinfunction "A148_158") (pintype "bidirectional"))
    )
    (net (code "114") (name "/IO_B64_L14_GC_AJ6_N") (class "Default")
      (node (ref "CONN_A2") (pin "161") (pinfunction "A154_161") (pintype "bidirectional"))
      (node (ref "CONN_C") (pin "159") (pinfunction "A150_159") (pintype "bidirectional"))
    )
    (net (code "115") (name "/IO_B64_L15_AD11_AK6_N") (class "Default")
      (node (ref "CONN_A2") (pin "166") (pinfunction "A164_166") (pintype "bidirectional"))
      (node (ref "CONN_C") (pin "165") (pinfunction "A162_165") (pintype "bidirectional"))
    )
    (net (code "116") (name "/IO_B64_L15_AD11_AK7_P") (class "Default")
      (node (ref "CONN_A2") (pin "165") (pinfunction "A162_165") (pintype "bidirectional"))
      (node (ref "CONN_C") (pin "164") (pinfunction "A160_164") (pintype "bidirectional"))
    )
    (net (code "117") (name "/IO_B64_L16_AD3_AF5_N") (class "Default")
      (node (ref "CONN_A2") (pin "168") (pinfunction "A168_168") (pintype "bidirectional"))
      (node (ref "CONN_C") (pin "167") (pinfunction "A166_167") (pintype "bidirectional"))
    )
    (net (code "118") (name "/IO_B64_L16_AD3_AF6_P") (class "Default")
      (node (ref "CONN_A2") (pin "167") (pinfunction "A166_167") (pintype "bidirectional"))
      (node (ref "CONN_C") (pin "166") (pinfunction "A164_166") (pintype "bidirectional"))
    )
    (net (code "119") (name "/IO_B64_L17_AD10_AJ5_P") (class "Default")
      (node (ref "CONN_A2") (pin "163") (pinfunction "A158_163") (pintype "bidirectional"))
      (node (ref "CONN_C") (pin "161") (pinfunction "A154_161") (pintype "bidirectional"))
    )
    (net (code "120") (name "/IO_B64_L17_AD10_AK5_N") (class "Default")
      (node (ref "CONN_A2") (pin "164") (pinfunction "A160_164") (pintype "bidirectional"))
      (node (ref "CONN_C") (pin "162") (pinfunction "A156_162") (pintype "bidirectional"))
    )
    (net (code "121") (name "/IO_B64_L18_AD2_AH4_P") (class "Default")
      (node (ref "CONN_A2") (pin "157") (pinfunction "A146_157") (pintype "bidirectional"))
      (node (ref "CONN_C") (pin "155") (pinfunction "A142_155") (pintype "bidirectional"))
    )
    (net (code "122") (name "/IO_B64_L18_AD2_AJ4_N") (class "Default")
      (node (ref "CONN_A2") (pin "158") (pinfunction "A148_158") (pintype "bidirectional"))
      (node (ref "CONN_C") (pin "156") (pinfunction "A144_156") (pintype "bidirectional"))
    )
    (net (code "123") (name "/IO_B64_L19_AD9_AK3_N") (class "Default")
      (node (ref "CONN_A2") (pin "156") (pinfunction "A144_156") (pintype "bidirectional"))
      (node (ref "CONN_C") (pin "154") (pinfunction "A140_154") (pintype "bidirectional"))
    )
    (net (code "124") (name "/IO_B64_L19_AD9_AK4_P") (class "Default")
      (node (ref "CONN_A2") (pin "155") (pinfunction "A142_155") (pintype "bidirectional"))
      (node (ref "CONN_C") (pin "153") (pinfunction "A138_153") (pintype "bidirectional"))
    )
    (net (code "125") (name "/IO_B64_L20_AD1_AH2_N") (class "Default")
      (node (ref "CONN_A2") (pin "154") (pinfunction "A140_154") (pintype "bidirectional"))
      (node (ref "CONN_C") (pin "151") (pinfunction "A134_151") (pintype "bidirectional"))
    )
    (net (code "126") (name "/IO_B64_L20_AD1_AH3_P") (class "Default")
      (node (ref "CONN_A2") (pin "153") (pinfunction "A138_153") (pintype "bidirectional"))
      (node (ref "CONN_C") (pin "150") (pinfunction "A132_150") (pintype "bidirectional"))
    )
    (net (code "127") (name "/IO_B64_L21_AD8_AJ2_P") (class "Default")
      (node (ref "CONN_A2") (pin "151") (pinfunction "A134_151") (pintype "bidirectional"))
      (node (ref "CONN_C") (pin "148") (pinfunction "A128_148") (pintype "bidirectional"))
    )
    (net (code "128") (name "/IO_B64_L21_AD8_AK2_N") (class "Default")
      (node (ref "CONN_A2") (pin "152") (pinfunction "A136_152") (pintype "bidirectional"))
      (node (ref "CONN_C") (pin "149") (pinfunction "A130_149") (pintype "bidirectional"))
    )
    (net (code "129") (name "/IO_B64_L22_AD0_AG1_P") (class "Default")
      (node (ref "CONN_A2") (pin "146") (pinfunction "A124_146") (pintype "bidirectional"))
      (node (ref "CONN_C") (pin "143") (pinfunction "A118_143") (pintype "bidirectional"))
    )
    (net (code "130") (name "/IO_B64_L22_AD0_AH1_N") (class "Default")
      (node (ref "CONN_A2") (pin "147") (pinfunction "A126_147") (pintype "bidirectional"))
      (node (ref "CONN_C") (pin "144") (pinfunction "A120_144") (pintype "bidirectional"))
    )
    (net (code "131") (name "/IO_B64_L23_AF3_P") (class "Default")
      (node (ref "CONN_A2") (pin "144") (pinfunction "A120_144") (pintype "bidirectional"))
      (node (ref "CONN_C") (pin "140") (pinfunction "A112_140") (pintype "bidirectional"))
    )
    (net (code "132") (name "/IO_B64_L23_AG3_N") (class "Default")
      (node (ref "CONN_A2") (pin "145") (pinfunction "A122_145") (pintype "bidirectional"))
      (node (ref "CONN_C") (pin "141") (pinfunction "A114_141") (pintype "bidirectional"))
    )
    (net (code "133") (name "/IO_B64_L24_AF1_N") (class "Default")
      (node (ref "CONN_A2") (pin "143") (pinfunction "A118_143") (pintype "bidirectional"))
      (node (ref "CONN_C") (pin "139") (pinfunction "A110_139") (pintype "bidirectional"))
    )
    (net (code "134") (name "/IO_B64_L24_AF2_P") (class "Default")
      (node (ref "CONN_A2") (pin "142") (pinfunction "A116_142") (pintype "bidirectional"))
      (node (ref "CONN_C") (pin "138") (pinfunction "A108_138") (pintype "bidirectional"))
    )
    (net (code "135") (name "/IO_B65_AE1_B128_REFCLK1_D26_N") (class "Default")
      (node (ref "CONN_A2") (pin "127") (pinfunction "A86_127") (pintype "bidirectional"))
      (node (ref "CONN_C") (pin "121") (pinfunction "A74_121") (pintype "bidirectional"))
    )
    (net (code "136") (name "/IO_B65_AE7_B128_REFCLK1_D25_P") (class "Default")
      (node (ref "CONN_A2") (pin "126") (pinfunction "A84_126") (pintype "bidirectional"))
      (node (ref "CONN_C") (pin "120") (pinfunction "A72_120") (pintype "bidirectional"))
    )
    (net (code "137") (name "/IO_B65_L1_AB13_P") (class "Default")
      (node (ref "CONN_A2") (pin "139") (pinfunction "A110_139") (pintype "bidirectional"))
      (node (ref "CONN_C") (pin "135") (pinfunction "A102_135") (pintype "bidirectional"))
    )
    (net (code "138") (name "/IO_B65_L1_AC13_N") (class "Default")
      (node (ref "CONN_A2") (pin "140") (pinfunction "A112_140") (pintype "bidirectional"))
      (node (ref "CONN_C") (pin "136") (pinfunction "A104_136") (pintype "bidirectional"))
    )
    (net (code "139") (name "/IO_B65_L2_AE13_P") (class "Default")
      (node (ref "CONN_A2") (pin "137") (pinfunction "A106_137") (pintype "bidirectional"))
      (node (ref "CONN_C") (pin "133") (pinfunction "A98_133") (pintype "bidirectional"))
    )
    (net (code "140") (name "/IO_B65_L2_AF13_N") (class "Default")
      (node (ref "CONN_A2") (pin "138") (pinfunction "A108_138") (pintype "bidirectional"))
      (node (ref "CONN_C") (pin "134") (pinfunction "A100_134") (pintype "bidirectional"))
    )
    (net (code "141") (name "/IO_B65_L3_AD15_AD12_B128_RX3_B29_P") (class "Default")
      (node (ref "CONN_A2") (pin "135") (pinfunction "A102_135") (pintype "bidirectional"))
      (node (ref "CONN_C") (pin "130") (pinfunction "A92_130") (pintype "bidirectional"))
    )
    (net (code "142") (name "/IO_B65_L3_AD15_AE12_B128_RX3_B30_N") (class "Default")
      (node (ref "CONN_A2") (pin "136") (pinfunction "A104_136") (pintype "bidirectional"))
      (node (ref "CONN_C") (pin "131") (pinfunction "A94_131") (pintype "bidirectional"))
    )
    (net (code "143") (name "/IO_B65_L4_AD7_AC11_B128_RX1_F29_P") (class "Default")
      (node (ref "CONN_A2") (pin "130") (pinfunction "A92_130") (pintype "bidirectional"))
      (node (ref "CONN_C") (pin "125") (pinfunction "A82_125") (pintype "bidirectional"))
    )
    (net (code "144") (name "/IO_B65_L4_AD7_AD11_B128_RX1_F30_N") (class "Default")
      (node (ref "CONN_A2") (pin "131") (pinfunction "A94_131") (pintype "bidirectional"))
      (node (ref "CONN_C") (pin "126") (pinfunction "A84_126") (pintype "bidirectional"))
    )
    (net (code "145") (name "/IO_B65_L5_AD14_AA11_B128_RX0_H30_N") (class "Default")
      (node (ref "CONN_A2") (pin "129") (pinfunction "A90_129") (pintype "bidirectional"))
      (node (ref "CONN_C") (pin "124") (pinfunction "A80_124") (pintype "bidirectional"))
    )
    (net (code "146") (name "/IO_B65_L5_AD14_AA12_B128_RX0_H29_P") (class "Default")
      (node (ref "CONN_A2") (pin "128") (pinfunction "A88_128") (pintype "bidirectional"))
      (node (ref "CONN_C") (pin "123") (pinfunction "A78_123") (pintype "bidirectional"))
    )
    (net (code "147") (name "/IO_B65_L6_AD6_AB10_N") (class "Default")
      (node (ref "CONN_A3") (pin "128") (pinfunction "A88_128") (pintype "bidirectional"))
      (node (ref "CONN_B") (pin "121") (pinfunction "A74_121") (pintype "bidirectional"))
    )
    (net (code "148") (name "/IO_B65_L6_AD6_AB11_P") (class "Default")
      (node (ref "CONN_A3") (pin "127") (pinfunction "A86_127") (pintype "bidirectional"))
      (node (ref "CONN_B") (pin "120") (pinfunction "A72_120") (pintype "bidirectional"))
    )
    (net (code "149") (name "/IO_B65_L7_AD13_AB9_P") (class "Default")
      (node (ref "CONN_A3") (pin "134") (pinfunction "A100_134") (pintype "bidirectional"))
      (node (ref "CONN_B") (pin "129") (pinfunction "A90_129") (pintype "bidirectional"))
    )
    (net (code "150") (name "/IO_B65_L7_AD13_AC9_N") (class "Default")
      (node (ref "CONN_A3") (pin "135") (pinfunction "A102_135") (pintype "bidirectional"))
      (node (ref "CONN_B") (pin "130") (pinfunction "A92_130") (pintype "bidirectional"))
    )
    (net (code "151") (name "/IO_B65_L8_AD5_AD10_P") (class "Default")
      (node (ref "CONN_A3") (pin "139") (pinfunction "A110_139") (pintype "bidirectional"))
      (node (ref "CONN_B") (pin "134") (pinfunction "A100_134") (pintype "bidirectional"))
    )
    (net (code "152") (name "/IO_B65_L8_AD5_AE10_N") (class "Default")
      (node (ref "CONN_A3") (pin "140") (pinfunction "A112_140") (pintype "bidirectional"))
      (node (ref "CONN_B") (pin "135") (pinfunction "A102_135") (pintype "bidirectional"))
    )
    (net (code "153") (name "/IO_B65_L9_AD12_AD9_P") (class "Default")
      (node (ref "CONN_A3") (pin "136") (pinfunction "A104_136") (pintype "bidirectional"))
      (node (ref "CONN_B") (pin "131") (pinfunction "A94_131") (pintype "bidirectional"))
    )
    (net (code "154") (name "/IO_B65_L9_AD12_AE9_N") (class "Default")
      (node (ref "CONN_A3") (pin "137") (pinfunction "A106_137") (pintype "bidirectional"))
      (node (ref "CONN_B") (pin "132") (pinfunction "A96_132") (pintype "bidirectional"))
    )
    (net (code "155") (name "/IO_B65_L10_AD4_AA7_N") (class "Default")
      (node (ref "CONN_A3") (pin "133") (pinfunction "A98_133") (pintype "bidirectional"))
      (node (ref "CONN_B") (pin "127") (pinfunction "A86_127") (pintype "bidirectional"))
    )
    (net (code "156") (name "/IO_B65_L10_AD4_AA8_P") (class "Default")
      (node (ref "CONN_A3") (pin "132") (pinfunction "A96_132") (pintype "bidirectional"))
      (node (ref "CONN_B") (pin "126") (pinfunction "A84_126") (pintype "bidirectional"))
    )
    (net (code "157") (name "/IO_B65_L11_GC_AC7_B128_RX2_D29_P") (class "Default")
      (node (ref "CONN_A2") (pin "133") (pinfunction "A98_133") (pintype "bidirectional"))
      (node (ref "CONN_C") (pin "128") (pinfunction "A88_128") (pintype "bidirectional"))
    )
    (net (code "158") (name "/IO_B65_L11_GC_AD7_B128_RX2_D30_N") (class "Default")
      (node (ref "CONN_A2") (pin "134") (pinfunction "A100_134") (pintype "bidirectional"))
      (node (ref "CONN_C") (pin "129") (pinfunction "A90_129") (pintype "bidirectional"))
    )
    (net (code "159") (name "/IO_B65_L12_GC_AB8_P") (class "Default")
      (node (ref "CONN_A3") (pin "129") (pinfunction "A90_129") (pintype "bidirectional"))
      (node (ref "CONN_B") (pin "123") (pinfunction "A78_123") (pintype "bidirectional"))
    )
    (net (code "160") (name "/IO_B65_L12_GC_AC8_N") (class "Default")
      (node (ref "CONN_A3") (pin "130") (pinfunction "A92_130") (pintype "bidirectional"))
      (node (ref "CONN_B") (pin "124") (pinfunction "A80_124") (pintype "bidirectional"))
    )
    (net (code "161") (name "/IO_B65_L13_GC_AB5_N") (class "Default")
      (node (ref "CONN_A3") (pin "153") (pinfunction "A138_153") (pintype "bidirectional"))
      (node (ref "CONN_B") (pin "150") (pinfunction "A132_150") (pintype "bidirectional"))
    )
    (net (code "162") (name "/IO_B65_L13_GC_AB6_P") (class "Default")
      (node (ref "CONN_A3") (pin "152") (pinfunction "A136_152") (pintype "bidirectional"))
      (node (ref "CONN_B") (pin "149") (pinfunction "A130_149") (pintype "bidirectional"))
    )
    (net (code "163") (name "/IO_B65_L14_GC_AC6_P") (class "Default")
      (node (ref "CONN_A3") (pin "162") (pinfunction "A156_162") (pintype "bidirectional"))
      (node (ref "CONN_B") (pin "161") (pinfunction "A154_161") (pintype "bidirectional"))
    )
    (net (code "164") (name "/IO_B65_L14_GC_AD6_N") (class "Default")
      (node (ref "CONN_A3") (pin "163") (pinfunction "A158_163") (pintype "bidirectional"))
      (node (ref "CONN_B") (pin "162") (pinfunction "A156_162") (pintype "bidirectional"))
    )
    (net (code "165") (name "/IO_B65_L15_AD11_AA5_N") (class "Default")
      (node (ref "CONN_A3") (pin "149") (pinfunction "A130_149") (pintype "bidirectional"))
      (node (ref "CONN_B") (pin "145") (pinfunction "A122_145") (pintype "bidirectional"))
    )
    (net (code "166") (name "/IO_B65_L15_AD11_AA6_P") (class "Default")
      (node (ref "CONN_A3") (pin "148") (pinfunction "A128_148") (pintype "bidirectional"))
      (node (ref "CONN_B") (pin "144") (pinfunction "A120_144") (pintype "bidirectional"))
    )
    (net (code "167") (name "/IO_B65_L16_AD3_AD5_P") (class "Default")
      (node (ref "CONN_A3") (pin "143") (pinfunction "A118_143") (pintype "bidirectional"))
      (node (ref "CONN_B") (pin "139") (pinfunction "A110_139") (pintype "bidirectional"))
    )
    (net (code "168") (name "/IO_B65_L16_AD3_AE5_N") (class "Default")
      (node (ref "CONN_A3") (pin "144") (pinfunction "A120_144") (pintype "bidirectional"))
      (node (ref "CONN_B") (pin "140") (pinfunction "A112_140") (pintype "bidirectional"))
    )
    (net (code "169") (name "/IO_B65_L17_AD10_AD4_P") (class "Default")
      (node (ref "CONN_A3") (pin "141") (pinfunction "A114_141") (pintype "bidirectional"))
      (node (ref "CONN_B") (pin "136") (pinfunction "A104_136") (pintype "bidirectional"))
    )
    (net (code "170") (name "/IO_B65_L17_AD10_AE4_N") (class "Default")
      (node (ref "CONN_A3") (pin "142") (pinfunction "A116_142") (pintype "bidirectional"))
      (node (ref "CONN_B") (pin "137") (pinfunction "A106_137") (pintype "bidirectional"))
    )
    (net (code "171") (name "/IO_B65_L18_AD2_AB4_P") (class "Default")
      (node (ref "CONN_A3") (pin "145") (pinfunction "A122_145") (pintype "bidirectional"))
      (node (ref "CONN_B") (pin "141") (pinfunction "A114_141") (pintype "bidirectional"))
    )
    (net (code "172") (name "/IO_B65_L18_AD2_AC4_N") (class "Default")
      (node (ref "CONN_A3") (pin "146") (pinfunction "A124_146") (pintype "bidirectional"))
      (node (ref "CONN_B") (pin "142") (pinfunction "A116_142") (pintype "bidirectional"))
    )
    (net (code "173") (name "/IO_B65_L19_AD9_AB3_P") (class "Default")
      (node (ref "CONN_A3") (pin "160") (pinfunction "A152_160") (pintype "bidirectional"))
      (node (ref "CONN_B") (pin "158") (pinfunction "A148_158") (pintype "bidirectional"))
    )
    (net (code "174") (name "/IO_B65_L19_AD9_AC3_N") (class "Default")
      (node (ref "CONN_A3") (pin "161") (pinfunction "A154_161") (pintype "bidirectional"))
      (node (ref "CONN_B") (pin "159") (pinfunction "A150_159") (pintype "bidirectional"))
    )
    (net (code "175") (name "/IO_B65_L20_AD1_AE2_N") (class "Default")
      (node (ref "CONN_A3") (pin "151") (pinfunction "A134_151") (pintype "bidirectional"))
      (node (ref "CONN_B") (pin "147") (pinfunction "A126_147") (pintype "bidirectional"))
    )
    (net (code "176") (name "/IO_B65_L20_AD1_AE3_P") (class "Default")
      (node (ref "CONN_A3") (pin "150") (pinfunction "A132_150") (pintype "bidirectional"))
      (node (ref "CONN_B") (pin "146") (pinfunction "A124_146") (pintype "bidirectional"))
    )
    (net (code "177") (name "/IO_B65_L21_AD8_AC2_P") (class "Default")
      (node (ref "CONN_A3") (pin "155") (pinfunction "A142_155") (pintype "bidirectional"))
      (node (ref "CONN_B") (pin "152") (pinfunction "A136_152") (pintype "bidirectional"))
    )
    (net (code "178") (name "/IO_B65_L21_AD8_AD2_N") (class "Default")
      (node (ref "CONN_A3") (pin "156") (pinfunction "A144_156") (pintype "bidirectional"))
      (node (ref "CONN_B") (pin "153") (pinfunction "A138_153") (pintype "bidirectional"))
    )
    (net (code "179") (name "/IO_B65_L22_AD0_AC1_P") (class "Default")
      (node (ref "CONN_A3") (pin "157") (pinfunction "A146_157") (pintype "bidirectional"))
      (node (ref "CONN_B") (pin "155") (pinfunction "A142_155") (pintype "bidirectional"))
    )
    (net (code "180") (name "/IO_B65_L22_AD0_AD1_N") (class "Default")
      (node (ref "CONN_A3") (pin "158") (pinfunction "A148_158") (pintype "bidirectional"))
      (node (ref "CONN_B") (pin "156") (pinfunction "A144_156") (pintype "bidirectional"))
    )
    (net (code "181") (name "/IO_B65_L23_AA2_N") (class "Default")
      (node (ref "CONN_A3") (pin "168") (pinfunction "A168_168") (pintype "bidirectional"))
      (node (ref "CONN_B") (pin "167") (pinfunction "A166_167") (pintype "bidirectional"))
    )
    (net (code "182") (name "/IO_B65_L23_SCLK_AA3_P") (class "Default")
      (node (ref "CONN_A3") (pin "167") (pinfunction "A166_167") (pintype "bidirectional"))
      (node (ref "CONN_B") (pin "166") (pinfunction "A164_166") (pintype "bidirectional"))
    )
    (net (code "183") (name "/IO_B65_L24_AB1_N") (class "Default")
      (node (ref "CONN_A3") (pin "166") (pinfunction "A164_166") (pintype "bidirectional"))
      (node (ref "CONN_B") (pin "165") (pinfunction "A162_165") (pintype "bidirectional"))
    )
    (net (code "184") (name "/IO_B65_L24_SDA_AA1_P") (class "Default")
      (node (ref "CONN_A3") (pin "165") (pinfunction "A162_165") (pintype "bidirectional"))
      (node (ref "CONN_B") (pin "164") (pinfunction "A160_164") (pintype "bidirectional"))
    )
    (net (code "185") (name "/IO_B66_L1_Y3_N") (class "Default")
      (node (ref "CONN_A2") (pin "56") (pinfunction "A111_56") (pintype "bidirectional"))
      (node (ref "CONN_C") (pin "51") (pinfunction "A101_51") (pintype "bidirectional"))
    )
    (net (code "186") (name "/IO_B66_L1_Y4_P") (class "Default")
      (node (ref "CONN_A2") (pin "55") (pinfunction "A109_55") (pintype "bidirectional"))
      (node (ref "CONN_C") (pin "50") (pinfunction "A99_50") (pintype "bidirectional"))
    )
    (net (code "187") (name "/IO_B66_L2_Y1_N") (class "Default")
      (node (ref "CONN_A2") (pin "54") (pinfunction "A107_54") (pintype "bidirectional"))
      (node (ref "CONN_C") (pin "49") (pinfunction "A97_49") (pintype "bidirectional"))
    )
    (net (code "188") (name "/IO_B66_L2_Y2_P") (class "Default")
      (node (ref "CONN_A2") (pin "53") (pinfunction "A105_53") (pintype "bidirectional"))
      (node (ref "CONN_C") (pin "48") (pinfunction "A95_48") (pintype "bidirectional"))
    )
    (net (code "189") (name "/IO_B66_L3_AD15_W1_B128_TX2_C28_N") (class "Default")
      (node (ref "CONN_A2") (pin "49") (pinfunction "A97_49") (pintype "bidirectional"))
      (node (ref "CONN_C") (pin "44") (pinfunction "A87_44") (pintype "bidirectional"))
    )
    (net (code "190") (name "/IO_B66_L3_AD15_W2_B128_TX2_C27_P") (class "Default")
      (node (ref "CONN_A2") (pin "48") (pinfunction "A95_48") (pintype "bidirectional"))
      (node (ref "CONN_C") (pin "43") (pinfunction "A85_43") (pintype "bidirectional"))
    )
    (net (code "191") (name "/IO_B66_L4_AD7_V1_B128_TX1_E28_N") (class "Default")
      (node (ref "CONN_A2") (pin "47") (pinfunction "A93_47") (pintype "bidirectional"))
      (node (ref "CONN_C") (pin "41") (pinfunction "A81_41") (pintype "bidirectional"))
    )
    (net (code "192") (name "/IO_B66_L4_AD7_V2_B128_TX1_E27_P") (class "Default")
      (node (ref "CONN_A2") (pin "46") (pinfunction "A91_46") (pintype "bidirectional"))
      (node (ref "CONN_C") (pin "40") (pinfunction "A79_40") (pintype "bidirectional"))
    )
    (net (code "193") (name "/IO_B66_L5_AD14_U2_B128_TX0_G27_P") (class "Default")
      (node (ref "CONN_A2") (pin "44") (pinfunction "A87_44") (pintype "bidirectional"))
      (node (ref "CONN_C") (pin "38") (pinfunction "A75_38") (pintype "bidirectional"))
    )
    (net (code "194") (name "/IO_B66_L5_AD14_U3_B128_TX0_G28_N") (class "Default")
      (node (ref "CONN_A2") (pin "45") (pinfunction "A89_45") (pintype "bidirectional"))
      (node (ref "CONN_C") (pin "39") (pinfunction "A77_39") (pintype "bidirectional"))
    )
    (net (code "195") (name "/IO_B66_L6_AD6_T1_P") (class "Default")
      (node (ref "CONN_A3") (pin "45") (pinfunction "A89_45") (pintype "bidirectional"))
      (node (ref "CONN_B") (pin "38") (pinfunction "A75_38") (pintype "bidirectional"))
    )
    (net (code "196") (name "/IO_B66_L6_AD6_U1_N") (class "Default")
      (node (ref "CONN_A3") (pin "46") (pinfunction "A91_46") (pintype "bidirectional"))
      (node (ref "CONN_B") (pin "39") (pinfunction "A77_39") (pintype "bidirectional"))
    )
    (net (code "197") (name "/IO_B66_L7_AD13_W5_P") (class "Default")
      (node (ref "CONN_A3") (pin "47") (pinfunction "A93_47") (pintype "bidirectional"))
      (node (ref "CONN_B") (pin "41") (pinfunction "A81_41") (pintype "bidirectional"))
    )
    (net (code "198") (name "/IO_B66_L7_AD13_Y5_N") (class "Default")
      (node (ref "CONN_A3") (pin "48") (pinfunction "A95_48") (pintype "bidirectional"))
      (node (ref "CONN_B") (pin "42") (pinfunction "A83_42") (pintype "bidirectional"))
    )
    (net (code "199") (name "/IO_B66_L8_AD5_V4_P") (class "Default")
      (node (ref "CONN_A3") (pin "50") (pinfunction "A99_50") (pintype "bidirectional"))
      (node (ref "CONN_B") (pin "44") (pinfunction "A87_44") (pintype "bidirectional"))
    )
    (net (code "200") (name "/IO_B66_L8_AD5_W4_N") (class "Default")
      (node (ref "CONN_A3") (pin "51") (pinfunction "A101_51") (pintype "bidirectional"))
      (node (ref "CONN_B") (pin "45") (pinfunction "A89_45") (pintype "bidirectional"))
    )
    (net (code "201") (name "/IO_B66_L9_AD12_U4_N") (class "Default")
      (node (ref "CONN_A3") (pin "53") (pinfunction "A105_53") (pintype "bidirectional"))
      (node (ref "CONN_B") (pin "47") (pinfunction "A93_47") (pintype "bidirectional"))
    )
    (net (code "202") (name "/IO_B66_L9_AD12_U5_P") (class "Default")
      (node (ref "CONN_A3") (pin "52") (pinfunction "A103_52") (pintype "bidirectional"))
      (node (ref "CONN_B") (pin "46") (pinfunction "A91_46") (pintype "bidirectional"))
    )
    (net (code "203") (name "/IO_B66_L10_AD4_U6_N") (class "Default")
      (node (ref "CONN_A3") (pin "55") (pinfunction "A109_55") (pintype "bidirectional"))
      (node (ref "CONN_B") (pin "50") (pinfunction "A99_50") (pintype "bidirectional"))
    )
    (net (code "204") (name "/IO_B66_L10_AD4_U7_P") (class "Default")
      (node (ref "CONN_A3") (pin "54") (pinfunction "A107_54") (pintype "bidirectional"))
      (node (ref "CONN_B") (pin "49") (pinfunction "A97_49") (pintype "bidirectional"))
    )
    (net (code "205") (name "/IO_B66_L11_GC_V6_B128_TX3_A28_N") (class "Default")
      (node (ref "CONN_A2") (pin "51") (pinfunction "A101_51") (pintype "bidirectional"))
      (node (ref "CONN_C") (pin "46") (pinfunction "A91_46") (pintype "bidirectional"))
    )
    (net (code "206") (name "/IO_B66_L11_GC_V7_B128_TX3_A27_P") (class "Default")
      (node (ref "CONN_A2") (pin "50") (pinfunction "A99_50") (pintype "bidirectional"))
      (node (ref "CONN_C") (pin "45") (pinfunction "A89_45") (pintype "bidirectional"))
    )
    (net (code "207") (name "/IO_B66_L12_GC_W6_N") (class "Default")
      (node (ref "CONN_A3") (pin "38") (pinfunction "A75_38") (pintype "bidirectional"))
      (node (ref "CONN_B") (pin "30") (pinfunction "A59_30") (pintype "bidirectional"))
    )
    (net (code "208") (name "/IO_B66_L12_GC_W7_P") (class "Default")
      (node (ref "CONN_A3") (pin "37") (pinfunction "A73_37") (pintype "bidirectional"))
      (node (ref "CONN_B") (pin "29") (pinfunction "A57_29") (pintype "bidirectional"))
    )
    (net (code "209") (name "/IO_B66_L13_GC_U8_P") (class "Default")
      (node (ref "CONN_A3") (pin "66") (pinfunction "A131_66") (pintype "bidirectional"))
      (node (ref "CONN_B") (pin "62") (pinfunction "A123_62") (pintype "bidirectional"))
    )
    (net (code "210") (name "/IO_B66_L13_GC_V8_N") (class "Default")
      (node (ref "CONN_A3") (pin "67") (pinfunction "A133_67") (pintype "bidirectional"))
      (node (ref "CONN_B") (pin "63") (pinfunction "A125_63") (pintype "bidirectional"))
    )
    (net (code "211") (name "/IO_B66_L14_GC_Y8_N") (class "Default")
      (node (ref "CONN_A3") (pin "79") (pinfunction "A157_79") (pintype "bidirectional"))
      (node (ref "CONN_B") (pin "77") (pinfunction "A153_77") (pintype "bidirectional"))
    )
    (net (code "212") (name "/IO_B66_L14_GC_Y9_P") (class "Default")
      (node (ref "CONN_A3") (pin "78") (pinfunction "A155_78") (pintype "bidirectional"))
      (node (ref "CONN_B") (pin "76") (pinfunction "A151_76") (pintype "bidirectional"))
    )
    (net (code "213") (name "/IO_B66_L15_AD11_U11_P") (class "Default")
      (node (ref "CONN_A3") (pin "61") (pinfunction "A121_61") (pintype "bidirectional"))
      (node (ref "CONN_B") (pin "56") (pinfunction "A111_56") (pintype "bidirectional"))
    )
    (net (code "214") (name "/IO_B66_L15_AD11_V11_N") (class "Default")
      (node (ref "CONN_A3") (pin "62") (pinfunction "A123_62") (pintype "bidirectional"))
      (node (ref "CONN_B") (pin "57") (pinfunction "A113_57") (pintype "bidirectional"))
    )
    (net (code "215") (name "/IO_B66_L16_AD3_W10_N") (class "Default")
      (node (ref "CONN_A3") (pin "64") (pinfunction "A127_64") (pintype "bidirectional"))
      (node (ref "CONN_B") (pin "60") (pinfunction "A119_60") (pintype "bidirectional"))
    )
    (net (code "216") (name "/IO_B66_L16_AD3_W11_P") (class "Default")
      (node (ref "CONN_A3") (pin "63") (pinfunction "A125_63") (pintype "bidirectional"))
      (node (ref "CONN_B") (pin "59") (pinfunction "A117_59") (pintype "bidirectional"))
    )
    (net (code "217") (name "/IO_B66_L17_AD10_U9_P") (class "Default")
      (node (ref "CONN_A3") (pin "56") (pinfunction "A111_56") (pintype "bidirectional"))
      (node (ref "CONN_B") (pin "51") (pinfunction "A101_51") (pintype "bidirectional"))
    )
    (net (code "218") (name "/IO_B66_L17_AD10_V9_N") (class "Default")
      (node (ref "CONN_A3") (pin "57") (pinfunction "A113_57") (pintype "bidirectional"))
      (node (ref "CONN_B") (pin "52") (pinfunction "A103_52") (pintype "bidirectional"))
    )
    (net (code "219") (name "/IO_B66_L18_AD2_T11_P") (class "Default")
      (node (ref "CONN_A3") (pin "59") (pinfunction "A117_59") (pintype "bidirectional"))
      (node (ref "CONN_B") (pin "54") (pinfunction "A107_54") (pintype "bidirectional"))
    )
    (net (code "220") (name "/IO_B66_L18_AD2_U10_N") (class "Default")
      (node (ref "CONN_A3") (pin "60") (pinfunction "A119_60") (pintype "bidirectional"))
      (node (ref "CONN_B") (pin "55") (pinfunction "A109_55") (pintype "bidirectional"))
    )
    (net (code "221") (name "/IO_B66_L19_AD9_R10_P") (class "Default")
      (node (ref "CONN_A3") (pin "68") (pinfunction "A135_68") (pintype "bidirectional"))
      (node (ref "CONN_B") (pin "65") (pinfunction "A129_65") (pintype "bidirectional"))
    )
    (net (code "222") (name "/IO_B66_L19_AD9_T10_N") (class "Default")
      (node (ref "CONN_A3") (pin "69") (pinfunction "A137_69") (pintype "bidirectional"))
      (node (ref "CONN_B") (pin "66") (pinfunction "A131_66") (pintype "bidirectional"))
    )
    (net (code "223") (name "/IO_B66_L20_AD1_P10_N") (class "Default")
      (node (ref "CONN_A3") (pin "71") (pinfunction "A141_71") (pintype "bidirectional"))
      (node (ref "CONN_B") (pin "68") (pinfunction "A135_68") (pintype "bidirectional"))
    )
    (net (code "224") (name "/IO_B66_L20_AD1_P11_P") (class "Default")
      (node (ref "CONN_A3") (pin "70") (pinfunction "A139_70") (pintype "bidirectional"))
      (node (ref "CONN_B") (pin "67") (pinfunction "A133_67") (pintype "bidirectional"))
    )
    (net (code "225") (name "/IO_B66_L21_AD8_M12_N") (class "Default")
      (node (ref "CONN_A3") (pin "76") (pinfunction "A151_76") (pintype "bidirectional"))
      (node (ref "CONN_B") (pin "74") (pinfunction "A147_74") (pintype "bidirectional"))
    )
    (net (code "226") (name "/IO_B66_L21_AD8_N12_P") (class "Default")
      (node (ref "CONN_A3") (pin "75") (pinfunction "A149_75") (pintype "bidirectional"))
      (node (ref "CONN_B") (pin "73") (pinfunction "A145_73") (pintype "bidirectional"))
    )
    (net (code "227") (name "/IO_B66_L22_AD0_M10_N") (class "Default")
      (node (ref "CONN_A3") (pin "74") (pinfunction "A147_74") (pintype "bidirectional"))
      (node (ref "CONN_B") (pin "71") (pinfunction "A141_71") (pintype "bidirectional"))
    )
    (net (code "228") (name "/IO_B66_L22_AD0_N10_P") (class "Default")
      (node (ref "CONN_A3") (pin "73") (pinfunction "A145_73") (pintype "bidirectional"))
      (node (ref "CONN_B") (pin "70") (pinfunction "A139_70") (pintype "bidirectional"))
    )
    (net (code "229") (name "/IO_B66_L23_L11_N") (class "Default")
      (node (ref "CONN_A3") (pin "81") (pinfunction "A161_81") (pintype "bidirectional"))
      (node (ref "CONN_B") (pin "80") (pinfunction "A159_80") (pintype "bidirectional"))
    )
    (net (code "230") (name "/IO_B66_L23_L12_P") (class "Default")
      (node (ref "CONN_A3") (pin "80") (pinfunction "A159_80") (pintype "bidirectional"))
      (node (ref "CONN_B") (pin "79") (pinfunction "A157_79") (pintype "bidirectional"))
    )
    (net (code "231") (name "/IO_B66_L24_K10_N") (class "Default")
      (node (ref "CONN_A3") (pin "84") (pinfunction "A167_84") (pintype "bidirectional"))
      (node (ref "CONN_B") (pin "83") (pinfunction "A165_83") (pintype "bidirectional"))
    )
    (net (code "232") (name "/IO_B66_L24_L10_P") (class "Default")
      (node (ref "CONN_A3") (pin "83") (pinfunction "A165_83") (pintype "bidirectional"))
      (node (ref "CONN_B") (pin "82") (pinfunction "A163_82") (pintype "bidirectional"))
    )
    (net (code "233") (name "/IO_B66_N11_B128_REFCLK0_F26_N") (class "Default")
      (node (ref "CONN_A2") (pin "42") (pinfunction "A83_42") (pintype "bidirectional"))
      (node (ref "CONN_C") (pin "36") (pinfunction "A71_36") (pintype "bidirectional"))
    )
    (net (code "234") (name "/IO_B66_Y10_B128_REFCLK0_F25_P") (class "Default")
      (node (ref "CONN_A2") (pin "41") (pinfunction "A81_41") (pintype "bidirectional"))
      (node (ref "CONN_C") (pin "35") (pinfunction "A69_35") (pintype "bidirectional"))
    )
    (net (code "235") (name "/JTAG_TCK") (class "Default")
      (node (ref "CONN_A") (pin "62") (pinfunction "A123_62") (pintype "bidirectional"))
    )
    (net (code "236") (name "/JTAG_TDI") (class "Default")
      (node (ref "CONN_A") (pin "59") (pinfunction "A117_59") (pintype "bidirectional"))
    )
    (net (code "237") (name "/JTAG_TDO") (class "Default")
      (node (ref "CONN_A") (pin "61") (pinfunction "A121_61") (pintype "bidirectional"))
    )
    (net (code "238") (name "/JTAG_TMS") (class "Default")
      (node (ref "CONN_A") (pin "60") (pinfunction "A119_60") (pintype "bidirectional"))
    )
    (net (code "239") (name "/MGTPS_REFCLK0_P25_P") (class "Default")
      (node (ref "CONN_A3") (pin "94") (pinfunction "A20_94") (pintype "bidirectional"))
      (node (ref "CONN_B") (pin "86") (pinfunction "A4_86") (pintype "bidirectional"))
    )
    (net (code "240") (name "/MGTPS_REFCLK0_P26_N") (class "Default")
      (node (ref "CONN_A3") (pin "95") (pinfunction "A22_95") (pintype "bidirectional"))
      (node (ref "CONN_B") (pin "87") (pinfunction "A6_87") (pintype "bidirectional"))
    )
    (net (code "241") (name "/MGTPS_REFCLK1_M25_P") (class "Default")
      (node (ref "CONN_A3") (pin "12") (pinfunction "A23_12") (pintype "bidirectional"))
      (node (ref "CONN_B") (pin "4") (pinfunction "A7_4") (pintype "bidirectional"))
    )
    (net (code "242") (name "/MGTPS_REFCLK1_M26_N") (class "Default")
      (node (ref "CONN_A3") (pin "13") (pinfunction "A25_13") (pintype "bidirectional"))
      (node (ref "CONN_B") (pin "5") (pinfunction "A9_5") (pintype "bidirectional"))
    )
    (net (code "243") (name "/MGTPS_RX0_T29_P") (class "Default")
      (node (ref "CONN_A3") (pin "100") (pinfunction "A32_100") (pintype "bidirectional"))
      (node (ref "CONN_B") (pin "92") (pinfunction "A16_92") (pintype "bidirectional"))
    )
    (net (code "244") (name "/MGTPS_RX0_T30_N") (class "Default")
      (node (ref "CONN_A3") (pin "102") (pinfunction "A36_102") (pintype "bidirectional"))
      (node (ref "CONN_B") (pin "94") (pinfunction "A20_94") (pintype "bidirectional"))
    )
    (net (code "245") (name "/MGTPS_RX1_P29_P") (class "Default")
      (node (ref "CONN_A3") (pin "104") (pinfunction "A40_104") (pintype "bidirectional"))
      (node (ref "CONN_B") (pin "96") (pinfunction "A24_96") (pintype "bidirectional"))
    )
    (net (code "246") (name "/MGTPS_RX1_P30_N") (class "Default")
      (node (ref "CONN_A3") (pin "106") (pinfunction "A44_106") (pintype "bidirectional"))
      (node (ref "CONN_B") (pin "98") (pinfunction "A28_98") (pintype "bidirectional"))
    )
    (net (code "247") (name "/MGTPS_RX2_M29_P") (class "Default")
      (node (ref "CONN_A3") (pin "108") (pinfunction "A48_108") (pintype "bidirectional"))
      (node (ref "CONN_B") (pin "100") (pinfunction "A32_100") (pintype "bidirectional"))
    )
    (net (code "248") (name "/MGTPS_RX2_M30_N") (class "Default")
      (node (ref "CONN_A3") (pin "110") (pinfunction "A52_110") (pintype "bidirectional"))
      (node (ref "CONN_B") (pin "102") (pinfunction "A36_102") (pintype "bidirectional"))
    )
    (net (code "249") (name "/MGTPS_RX3_K29_P") (class "Default")
      (node (ref "CONN_A3") (pin "112") (pinfunction "A56_112") (pintype "bidirectional"))
      (node (ref "CONN_B") (pin "104") (pinfunction "A40_104") (pintype "bidirectional"))
    )
    (net (code "250") (name "/MGTPS_RX3_K30_N") (class "Default")
      (node (ref "CONN_A3") (pin "114") (pinfunction "A60_114") (pintype "bidirectional"))
      (node (ref "CONN_B") (pin "106") (pinfunction "A44_106") (pintype "bidirectional"))
    )
    (net (code "251") (name "/MGTPS_TX0_R27_P") (class "Default")
      (node (ref "CONN_A3") (pin "15") (pinfunction "A29_15") (pintype "bidirectional"))
      (node (ref "CONN_B") (pin "7") (pinfunction "A13_7") (pintype "bidirectional"))
    )
    (net (code "252") (name "/MGTPS_TX0_R28_N") (class "Default")
      (node (ref "CONN_A3") (pin "17") (pinfunction "A33_17") (pintype "bidirectional"))
      (node (ref "CONN_B") (pin "9") (pinfunction "A17_9") (pintype "bidirectional"))
    )
    (net (code "253") (name "/MGTPS_TX1_N27_P") (class "Default")
      (node (ref "CONN_A3") (pin "19") (pinfunction "A37_19") (pintype "bidirectional"))
      (node (ref "CONN_B") (pin "11") (pinfunction "A21_11") (pintype "bidirectional"))
    )
    (net (code "254") (name "/MGTPS_TX1_N28_N") (class "Default")
      (node (ref "CONN_A3") (pin "21") (pinfunction "A41_21") (pintype "bidirectional"))
      (node (ref "CONN_B") (pin "13") (pinfunction "A25_13") (pintype "bidirectional"))
    )
    (net (code "255") (name "/MGTPS_TX2_L27_P") (class "Default")
      (node (ref "CONN_A3") (pin "23") (pinfunction "A45_23") (pintype "bidirectional"))
      (node (ref "CONN_B") (pin "15") (pinfunction "A29_15") (pintype "bidirectional"))
    )
    (net (code "256") (name "/MGTPS_TX2_L28_N") (class "Default")
      (node (ref "CONN_A3") (pin "25") (pinfunction "A49_25") (pintype "bidirectional"))
      (node (ref "CONN_B") (pin "17") (pinfunction "A33_17") (pintype "bidirectional"))
    )
    (net (code "257") (name "/MGTPS_TX3_J27_P") (class "Default")
      (node (ref "CONN_A3") (pin "27") (pinfunction "A53_27") (pintype "bidirectional"))
      (node (ref "CONN_B") (pin "19") (pinfunction "A37_19") (pintype "bidirectional"))
    )
    (net (code "258") (name "/MGTPS_TX3_J28_N") (class "Default")
      (node (ref "CONN_A3") (pin "29") (pinfunction "A57_29") (pintype "bidirectional"))
      (node (ref "CONN_B") (pin "21") (pinfunction "A41_21") (pintype "bidirectional"))
    )
    (net (code "259") (name "/MGT_B228_REFCLK0_R7_N") (class "Default")
      (node (ref "CONN_A2") (pin "96") (pinfunction "A24_96") (pintype "bidirectional"))
      (node (ref "CONN_C") (pin "90") (pinfunction "A12_90") (pintype "bidirectional"))
    )
    (net (code "260") (name "/MGT_B228_REFCLK0_R8_P") (class "Default")
      (node (ref "CONN_A2") (pin "95") (pinfunction "A22_95") (pintype "bidirectional"))
      (node (ref "CONN_C") (pin "89") (pinfunction "A10_89") (pintype "bidirectional"))
    )
    (net (code "261") (name "/MGT_B228_RX0_R3_N") (class "Default")
      (node (ref "CONN_A2") (pin "115") (pinfunction "A62_115") (pintype "bidirectional"))
      (node (ref "CONN_C") (pin "109") (pinfunction "A50_109") (pintype "bidirectional"))
    )
    (net (code "262") (name "/MGT_B228_RX0_R4_P") (class "Default")
      (node (ref "CONN_A2") (pin "114") (pinfunction "A60_114") (pintype "bidirectional"))
      (node (ref "CONN_C") (pin "108") (pinfunction "A48_108") (pintype "bidirectional"))
    )
    (net (code "263") (name "/MGT_B228_RX1_P1_N") (class "Default")
      (node (ref "CONN_A2") (pin "118") (pinfunction "A68_118") (pintype "bidirectional"))
      (node (ref "CONN_C") (pin "112") (pinfunction "A56_112") (pintype "bidirectional"))
    )
    (net (code "264") (name "/MGT_B228_RX1_P2_P") (class "Default")
      (node (ref "CONN_A2") (pin "117") (pinfunction "A66_117") (pintype "bidirectional"))
      (node (ref "CONN_C") (pin "111") (pinfunction "A54_111") (pintype "bidirectional"))
    )
    (net (code "265") (name "/MGT_B228_RX2_M1_N") (class "Default")
      (node (ref "CONN_A2") (pin "121") (pinfunction "A74_121") (pintype "bidirectional"))
      (node (ref "CONN_C") (pin "115") (pinfunction "A62_115") (pintype "bidirectional"))
    )
    (net (code "266") (name "/MGT_B228_RX2_M2_P") (class "Default")
      (node (ref "CONN_A2") (pin "120") (pinfunction "A72_120") (pintype "bidirectional"))
      (node (ref "CONN_C") (pin "114") (pinfunction "A60_114") (pintype "bidirectional"))
    )
    (net (code "267") (name "/MGT_B228_RX3_L3_N") (class "Default")
      (node (ref "CONN_A2") (pin "124") (pinfunction "A80_124") (pintype "bidirectional"))
      (node (ref "CONN_C") (pin "118") (pinfunction "A68_118") (pintype "bidirectional"))
    )
    (net (code "268") (name "/MGT_B228_RX3_L4_P") (class "Default")
      (node (ref "CONN_A2") (pin "123") (pinfunction "A78_123") (pintype "bidirectional"))
      (node (ref "CONN_C") (pin "117") (pinfunction "A66_117") (pintype "bidirectional"))
    )
    (net (code "269") (name "/MGT_B228_TX0_P5_N") (class "Default")
      (node (ref "CONN_A2") (pin "30") (pinfunction "A59_30") (pintype "bidirectional"))
      (node (ref "CONN_C") (pin "24") (pinfunction "A47_24") (pintype "bidirectional"))
    )
    (net (code "270") (name "/MGT_B228_TX0_P6_P") (class "Default")
      (node (ref "CONN_A2") (pin "29") (pinfunction "A57_29") (pintype "bidirectional"))
      (node (ref "CONN_C") (pin "23") (pinfunction "A45_23") (pintype "bidirectional"))
    )
    (net (code "271") (name "/MGT_B228_TX1_N3_N") (class "Default")
      (node (ref "CONN_A2") (pin "33") (pinfunction "A65_33") (pintype "bidirectional"))
      (node (ref "CONN_C") (pin "27") (pinfunction "A53_27") (pintype "bidirectional"))
    )
    (net (code "272") (name "/MGT_B228_TX1_N4_P") (class "Default")
      (node (ref "CONN_A2") (pin "32") (pinfunction "A63_32") (pintype "bidirectional"))
      (node (ref "CONN_C") (pin "26") (pinfunction "A51_26") (pintype "bidirectional"))
    )
    (net (code "273") (name "/MGT_B228_TX2_M5_N") (class "Default")
      (node (ref "CONN_A2") (pin "36") (pinfunction "A71_36") (pintype "bidirectional"))
      (node (ref "CONN_C") (pin "30") (pinfunction "A59_30") (pintype "bidirectional"))
    )
    (net (code "274") (name "/MGT_B228_TX2_M6_P") (class "Default")
      (node (ref "CONN_A2") (pin "35") (pinfunction "A69_35") (pintype "bidirectional"))
      (node (ref "CONN_C") (pin "29") (pinfunction "A57_29") (pintype "bidirectional"))
    )
    (net (code "275") (name "/MGT_B228_TX3_K5_N") (class "Default")
      (node (ref "CONN_A2") (pin "39") (pinfunction "A77_39") (pintype "bidirectional"))
      (node (ref "CONN_C") (pin "33") (pinfunction "A65_33") (pintype "bidirectional"))
    )
    (net (code "276") (name "/MGT_B228_TX3_K6_P") (class "Default")
      (node (ref "CONN_A2") (pin "38") (pinfunction "A75_38") (pintype "bidirectional"))
      (node (ref "CONN_C") (pin "32") (pinfunction "A63_32") (pintype "bidirectional"))
    )
    (net (code "277") (name "/MGT_B229_REFCLK0_L7_N") (class "Default")
      (node (ref "CONN_A2") (pin "93") (pinfunction "A18_93") (pintype "bidirectional"))
      (node (ref "CONN_C") (pin "87") (pinfunction "A6_87") (pintype "bidirectional"))
    )
    (net (code "278") (name "/MGT_B229_REFCLK0_L8_P") (class "Default")
      (node (ref "CONN_A2") (pin "92") (pinfunction "A16_92") (pintype "bidirectional"))
      (node (ref "CONN_C") (pin "86") (pinfunction "A4_86") (pintype "bidirectional"))
    )
    (net (code "279") (name "/MGT_B229_REFCLK1_J7_N") (class "Default")
      (node (ref "CONN_A2") (pin "9") (pinfunction "A17_9") (pintype "bidirectional"))
      (node (ref "CONN_C") (pin "3") (pinfunction "A5_3") (pintype "bidirectional"))
    )
    (net (code "280") (name "/MGT_B229_REFCLK1_J8_P") (class "Default")
      (node (ref "CONN_A2") (pin "8") (pinfunction "A15_8") (pintype "bidirectional"))
      (node (ref "CONN_C") (pin "2") (pinfunction "A3_2") (pintype "bidirectional"))
    )
    (net (code "281") (name "/MGT_B229_REFCLK1_N7_N") (class "Default")
      (node (ref "CONN_A2") (pin "11") (pinfunction "A21_11") (pintype "bidirectional"))
      (node (ref "CONN_C") (pin "5") (pinfunction "A9_5") (pintype "bidirectional"))
    )
    (net (code "282") (name "/MGT_B229_REFCLK1_N8_P") (class "Default")
      (node (ref "CONN_A2") (pin "10") (pinfunction "A19_10") (pintype "bidirectional"))
      (node (ref "CONN_C") (pin "4") (pinfunction "A7_4") (pintype "bidirectional"))
    )
    (net (code "283") (name "/MGT_B229_RX0_K1_N") (class "Default")
      (node (ref "CONN_A2") (pin "100") (pinfunction "A32_100") (pintype "bidirectional"))
      (node (ref "CONN_C") (pin "94") (pinfunction "A20_94") (pintype "bidirectional"))
    )
    (net (code "284") (name "/MGT_B229_RX0_K2_P") (class "Default")
      (node (ref "CONN_A2") (pin "98") (pinfunction "A28_98") (pintype "bidirectional"))
      (node (ref "CONN_C") (pin "92") (pinfunction "A16_92") (pintype "bidirectional"))
    )
    (net (code "285") (name "/MGT_B229_RX1_H1_N") (class "Default")
      (node (ref "CONN_A2") (pin "104") (pinfunction "A40_104") (pintype "bidirectional"))
      (node (ref "CONN_C") (pin "98") (pinfunction "A28_98") (pintype "bidirectional"))
    )
    (net (code "286") (name "/MGT_B229_RX1_H2_P") (class "Default")
      (node (ref "CONN_A2") (pin "102") (pinfunction "A36_102") (pintype "bidirectional"))
      (node (ref "CONN_C") (pin "96") (pinfunction "A24_96") (pintype "bidirectional"))
    )
    (net (code "287") (name "/MGT_B229_RX2_G3_N") (class "Default")
      (node (ref "CONN_A2") (pin "108") (pinfunction "A48_108") (pintype "bidirectional"))
      (node (ref "CONN_C") (pin "102") (pinfunction "A36_102") (pintype "bidirectional"))
    )
    (net (code "288") (name "/MGT_B229_RX2_G4_P") (class "Default")
      (node (ref "CONN_A2") (pin "106") (pinfunction "A44_106") (pintype "bidirectional"))
      (node (ref "CONN_C") (pin "100") (pinfunction "A32_100") (pintype "bidirectional"))
    )
    (net (code "289") (name "/MGT_B229_RX3_F1_N") (class "Default")
      (node (ref "CONN_A2") (pin "112") (pinfunction "A56_112") (pintype "bidirectional"))
      (node (ref "CONN_C") (pin "106") (pinfunction "A44_106") (pintype "bidirectional"))
    )
    (net (code "290") (name "/MGT_B229_RX3_F2_P") (class "Default")
      (node (ref "CONN_A2") (pin "110") (pinfunction "A52_110") (pintype "bidirectional"))
      (node (ref "CONN_C") (pin "104") (pinfunction "A40_104") (pintype "bidirectional"))
    )
    (net (code "291") (name "/MGT_B229_TX0_J3_N") (class "Default")
      (node (ref "CONN_A2") (pin "15") (pinfunction "A29_15") (pintype "bidirectional"))
      (node (ref "CONN_C") (pin "9") (pinfunction "A17_9") (pintype "bidirectional"))
    )
    (net (code "292") (name "/MGT_B229_TX0_J4_P") (class "Default")
      (node (ref "CONN_A2") (pin "13") (pinfunction "A25_13") (pintype "bidirectional"))
      (node (ref "CONN_C") (pin "7") (pinfunction "A13_7") (pintype "bidirectional"))
    )
    (net (code "293") (name "/MGT_B229_TX1_H5_N") (class "Default")
      (node (ref "CONN_A2") (pin "19") (pinfunction "A37_19") (pintype "bidirectional"))
      (node (ref "CONN_C") (pin "13") (pinfunction "A25_13") (pintype "bidirectional"))
    )
    (net (code "294") (name "/MGT_B229_TX1_H6_P") (class "Default")
      (node (ref "CONN_A2") (pin "17") (pinfunction "A33_17") (pintype "bidirectional"))
      (node (ref "CONN_C") (pin "11") (pinfunction "A21_11") (pintype "bidirectional"))
    )
    (net (code "295") (name "/MGT_B229_TX2_F5_N") (class "Default")
      (node (ref "CONN_A2") (pin "23") (pinfunction "A45_23") (pintype "bidirectional"))
      (node (ref "CONN_C") (pin "17") (pinfunction "A33_17") (pintype "bidirectional"))
    )
    (net (code "296") (name "/MGT_B229_TX2_F6_P") (class "Default")
      (node (ref "CONN_A2") (pin "21") (pinfunction "A41_21") (pintype "bidirectional"))
      (node (ref "CONN_C") (pin "15") (pinfunction "A29_15") (pintype "bidirectional"))
    )
    (net (code "297") (name "/MGT_B229_TX3_E3_N") (class "Default")
      (node (ref "CONN_A2") (pin "27") (pinfunction "A53_27") (pintype "bidirectional"))
      (node (ref "CONN_C") (pin "21") (pinfunction "A41_21") (pintype "bidirectional"))
    )
    (net (code "298") (name "/MGT_B229_TX3_E4_P") (class "Default")
      (node (ref "CONN_A2") (pin "25") (pinfunction "A49_25") (pintype "bidirectional"))
      (node (ref "CONN_C") (pin "19") (pinfunction "A37_19") (pintype "bidirectional"))
    )
    (net (code "299") (name "/MGT_B230_REFCLK0_G7_N") (class "Default")
      (node (ref "CONN_A3") (pin "98") (pinfunction "A28_98") (pintype "bidirectional"))
      (node (ref "CONN_B") (pin "90") (pinfunction "A12_90") (pintype "bidirectional"))
    )
    (net (code "300") (name "/MGT_B230_REFCLK0_G8_P") (class "Default")
      (node (ref "CONN_A3") (pin "97") (pinfunction "A26_97") (pintype "bidirectional"))
      (node (ref "CONN_B") (pin "89") (pinfunction "A10_89") (pintype "bidirectional"))
    )
    (net (code "301") (name "/MGT_B230_REFCLK1_E7_N") (class "Default")
      (node (ref "CONN_A3") (pin "11") (pinfunction "A21_11") (pintype "bidirectional"))
      (node (ref "CONN_B") (pin "3") (pinfunction "A5_3") (pintype "bidirectional"))
    )
    (net (code "302") (name "/MGT_B230_REFCLK1_E8_P") (class "Default")
      (node (ref "CONN_A3") (pin "10") (pinfunction "A19_10") (pintype "bidirectional"))
      (node (ref "CONN_B") (pin "2") (pinfunction "A3_2") (pintype "bidirectional"))
    )
    (net (code "303") (name "/MGT_B230_RX0_D1_N") (class "Default")
      (node (ref "CONN_A3") (pin "117") (pinfunction "A66_117") (pintype "bidirectional"))
      (node (ref "CONN_B") (pin "109") (pinfunction "A50_109") (pintype "bidirectional"))
    )
    (net (code "304") (name "/MGT_B230_RX0_D2_P") (class "Default")
      (node (ref "CONN_A3") (pin "116") (pinfunction "A64_116") (pintype "bidirectional"))
      (node (ref "CONN_B") (pin "108") (pinfunction "A48_108") (pintype "bidirectional"))
    )
    (net (code "305") (name "/MGT_B230_RX1_C3_N") (class "Default")
      (node (ref "CONN_A3") (pin "120") (pinfunction "A72_120") (pintype "bidirectional"))
      (node (ref "CONN_B") (pin "112") (pinfunction "A56_112") (pintype "bidirectional"))
    )
    (net (code "306") (name "/MGT_B230_RX1_C4_P") (class "Default")
      (node (ref "CONN_A3") (pin "119") (pinfunction "A70_119") (pintype "bidirectional"))
      (node (ref "CONN_B") (pin "111") (pinfunction "A54_111") (pintype "bidirectional"))
    )
    (net (code "307") (name "/MGT_B230_RX2_B1_N") (class "Default")
      (node (ref "CONN_A3") (pin "123") (pinfunction "A78_123") (pintype "bidirectional"))
      (node (ref "CONN_B") (pin "115") (pinfunction "A62_115") (pintype "bidirectional"))
    )
    (net (code "308") (name "/MGT_B230_RX2_B2_P") (class "Default")
      (node (ref "CONN_A3") (pin "122") (pinfunction "A76_122") (pintype "bidirectional"))
      (node (ref "CONN_B") (pin "114") (pinfunction "A60_114") (pintype "bidirectional"))
    )
    (net (code "309") (name "/MGT_B230_RX3_A3_N") (class "Default")
      (node (ref "CONN_A3") (pin "125") (pinfunction "A82_125") (pintype "bidirectional"))
      (node (ref "CONN_B") (pin "118") (pinfunction "A68_118") (pintype "bidirectional"))
    )
    (net (code "310") (name "/MGT_B230_RX3_A4_P") (class "Default")
      (node (ref "CONN_A3") (pin "124") (pinfunction "A80_124") (pintype "bidirectional"))
      (node (ref "CONN_B") (pin "117") (pinfunction "A66_117") (pintype "bidirectional"))
    )
    (net (code "311") (name "/MGT_B230_TX0_D5_N") (class "Default")
      (node (ref "CONN_A3") (pin "32") (pinfunction "A63_32") (pintype "bidirectional"))
      (node (ref "CONN_B") (pin "24") (pinfunction "A47_24") (pintype "bidirectional"))
    )
    (net (code "312") (name "/MGT_B230_TX0_D6_P") (class "Default")
      (node (ref "CONN_A3") (pin "31") (pinfunction "A61_31") (pintype "bidirectional"))
      (node (ref "CONN_B") (pin "23") (pinfunction "A45_23") (pintype "bidirectional"))
    )
    (net (code "313") (name "/MGT_B230_TX1_C7_N") (class "Default")
      (node (ref "CONN_A3") (pin "35") (pinfunction "A69_35") (pintype "bidirectional"))
      (node (ref "CONN_B") (pin "27") (pinfunction "A53_27") (pintype "bidirectional"))
    )
    (net (code "314") (name "/MGT_B230_TX1_C8_P") (class "Default")
      (node (ref "CONN_A3") (pin "34") (pinfunction "A67_34") (pintype "bidirectional"))
      (node (ref "CONN_B") (pin "26") (pinfunction "A51_26") (pintype "bidirectional"))
    )
    (net (code "315") (name "/MGT_B230_TX2_B5_N") (class "Default")
      (node (ref "CONN_A3") (pin "41") (pinfunction "A81_41") (pintype "bidirectional"))
      (node (ref "CONN_B") (pin "33") (pinfunction "A65_33") (pintype "bidirectional"))
    )
    (net (code "316") (name "/MGT_B230_TX2_B6_P") (class "Default")
      (node (ref "CONN_A3") (pin "40") (pinfunction "A79_40") (pintype "bidirectional"))
      (node (ref "CONN_B") (pin "32") (pinfunction "A63_32") (pintype "bidirectional"))
    )
    (net (code "317") (name "/MGT_B230_TX3_A7_N") (class "Default")
      (node (ref "CONN_A3") (pin "43") (pinfunction "A85_43") (pintype "bidirectional"))
      (node (ref "CONN_B") (pin "36") (pinfunction "A71_36") (pintype "bidirectional"))
    )
    (net (code "318") (name "/MGT_B230_TX3_A8_P") (class "Default")
      (node (ref "CONN_A3") (pin "42") (pinfunction "A83_42") (pintype "bidirectional"))
      (node (ref "CONN_B") (pin "35") (pinfunction "A69_35") (pintype "bidirectional"))
    )
    (net (code "319") (name "/N$3") (class "Default")
      (node (ref "IC2") (pin "1") (pinfunction "D1+_1") (pintype "bidirectional"))
      (node (ref "RN1") (pin "8") (pinfunction "2_8") (pintype "passive"))
    )
    (net (code "320") (name "/N$7") (class "Default")
      (node (ref "IC2") (pin "3") (pinfunction "D2+_3") (pintype "bidirectional"))
      (node (ref "RN1") (pin "7") (pinfunction "2_7") (pintype "passive"))
    )
    (net (code "321") (name "/N$10") (class "Default")
      (node (ref "IC3") (pin "1") (pinfunction "D1+_1") (pintype "bidirectional"))
      (node (ref "RN1") (pin "6") (pinfunction "2_6") (pintype "passive"))
    )
    (net (code "322") (name "/N$11") (class "Default")
      (node (ref "IC3") (pin "3") (pinfunction "D2+_3") (pintype "bidirectional"))
      (node (ref "RN1") (pin "5") (pinfunction "2_5") (pintype "passive"))
    )
    (net (code "323") (name "/N$19") (class "Default")
      (node (ref "CONN_A") (pin "39") (pinfunction "A77_39") (pintype "bidirectional"))
    )
    (net (code "324") (name "/N$22") (class "Default")
      (node (ref "CONN_A") (pin "21") (pinfunction "A41_21") (pintype "bidirectional"))
    )
    (net (code "325") (name "/PS_DONE") (class "Default")
      (node (ref "CONN_A") (pin "149") (pinfunction "A130_149") (pintype "bidirectional"))
      (node (ref "Q3") (pin "2") (pinfunction "TR1_GATE_2") (pintype "bidirectional"))
      (node (ref "R2") (pin "2") (pinfunction "2_2") (pintype "passive"))
    )
    (net (code "326") (name "/PS_MIO38_UARTRX") (class "Default")
      (node (ref "CONN_A") (pin "53") (pinfunction "A105_53") (pintype "bidirectional"))
    )
    (net (code "327") (name "/PS_MIO39_UARTTX") (class "Default")
      (node (ref "CONN_A") (pin "54") (pinfunction "A107_54") (pintype "bidirectional"))
    )
    (net (code "328") (name "/PS_MIO40") (class "Default")
      (node (ref "CONN_A") (pin "125") (pinfunction "A82_125") (pintype "bidirectional"))
      (node (ref "CONN_A1") (pin "157") (pinfunction "A146_157") (pintype "bidirectional"))
    )
    (net (code "329") (name "/PS_MIO41") (class "Default")
      (node (ref "CONN_A") (pin "126") (pinfunction "A84_126") (pintype "bidirectional"))
      (node (ref "CONN_A1") (pin "158") (pinfunction "A148_158") (pintype "bidirectional"))
    )
    (net (code "330") (name "/PS_MIO42_PERST#") (class "Default")
      (node (ref "CONN_A") (pin "136") (pinfunction "A104_136") (pintype "bidirectional"))
      (node (ref "CONN_A1") (pin "167") (pinfunction "A166_167") (pintype "bidirectional"))
    )
    (net (code "331") (name "/PS_MIO43") (class "Default")
      (node (ref "CONN_A") (pin "137") (pinfunction "A106_137") (pintype "bidirectional"))
      (node (ref "CONN_A1") (pin "168") (pinfunction "A168_168") (pintype "bidirectional"))
    )
    (net (code "332") (name "/PS_MIO44") (class "Default")
      (node (ref "CONN_A") (pin "134") (pinfunction "A100_134") (pintype "bidirectional"))
      (node (ref "CONN_A1") (pin "165") (pinfunction "A162_165") (pintype "bidirectional"))
    )
    (net (code "333") (name "/PS_MIO45_SDCD#") (class "Default")
      (node (ref "CONN_A") (pin "133") (pinfunction "A98_133") (pintype "bidirectional"))
      (node (ref "CONN_A1") (pin "164") (pinfunction "A160_164") (pintype "bidirectional"))
    )
    (net (code "334") (name "/PS_MIO46_SDD0") (class "Default")
      (node (ref "CONN_A") (pin "48") (pinfunction "A95_48") (pintype "bidirectional"))
      (node (ref "SDIO_LEVEL_SHIFTER") (pin "6") (pinfunction "DAT0A_6") (pintype "bidirectional"))
    )
    (net (code "335") (name "/PS_MIO47_SDD1") (class "Default")
      (node (ref "CONN_A") (pin "49") (pinfunction "A97_49") (pintype "bidirectional"))
      (node (ref "SDIO_LEVEL_SHIFTER") (pin "7") (pinfunction "DAT1A_7") (pintype "bidirectional"))
    )
    (net (code "336") (name "/PS_MIO48_SDD2") (class "Default")
      (node (ref "CONN_A") (pin "51") (pinfunction "A101_51") (pintype "bidirectional"))
      (node (ref "SDIO_LEVEL_SHIFTER") (pin "1") (pinfunction "DAT2A_1") (pintype "bidirectional"))
    )
    (net (code "337") (name "/PS_MIO49_SDD3") (class "Default")
      (node (ref "SDIO_LEVEL_SHIFTER") (pin "3") (pinfunction "DAT3A_3") (pintype "bidirectional"))
    )
    (net (code "338") (name "/PS_MIO50_SDCMD") (class "Default")
      (node (ref "CONN_A") (pin "47") (pinfunction "A93_47") (pintype "bidirectional"))
      (node (ref "SDIO_LEVEL_SHIFTER") (pin "4") (pinfunction "CMDA_4") (pintype "bidirectional"))
    )
    (net (code "339") (name "/PS_MIO51_SDCLK") (class "Default")
      (node (ref "CONN_A") (pin "46") (pinfunction "A91_46") (pintype "bidirectional"))
      (node (ref "R900") (pin "1") (pinfunction "1_1") (pintype "passive"))
      (node (ref "R900") (pin "2") (pinfunction "2_2") (pintype "passive"))
      (node (ref "SDIO_LEVEL_SHIFTER") (pin "9") (pinfunction "CLKA_9") (pintype "bidirectional"))
    )
    (net (code "340") (name "/PS_MIO_49_SDD3") (class "Default")
      (node (ref "CONN_A") (pin "52") (pinfunction "A103_52") (pintype "bidirectional"))
    )
    (net (code "341") (name "/PS_POR#") (class "Default")
      (node (ref "C12") (pin "1") (pinfunction "1_1") (pintype "passive"))
      (node (ref "CONN_A") (pin "150") (pinfunction "A132_150") (pintype "bidirectional"))
      (node (ref "SW1") (pin "P$1") (pinfunction "P$1_P$1") (pintype "passive"))
    )
    (net (code "342") (name "/PS_SRST#") (class "Default")
      (node (ref "C2") (pin "1") (pinfunction "1_1") (pintype "passive"))
      (node (ref "CONN_A") (pin "146") (pinfunction "A124_146") (pintype "bidirectional"))
      (node (ref "JTAG") (pin "14") (pinfunction "14_14") (pintype "passive"))
      (node (ref "SW2") (pin "P$1") (pinfunction "P$1_P$1") (pintype "passive"))
    )
    (net (code "343") (name "/PWR_EN") (class "Default")
      (node (ref "CONN_A") (pin "89") (pinfunction "A10_89") (pintype "bidirectional"))
      (node (ref "D1") (pin "1") (pinfunction "K_1") (pintype "bidirectional"))
      (node (ref "R5") (pin "2") (pinfunction "2_2") (pintype "passive"))
      (node (ref "R6") (pin "2") (pinfunction "2_2") (pintype "passive"))
    )
    (net (code "344") (name "/PWR_GOOD") (class "Default")
      (node (ref "CONN_A") (pin "90") (pinfunction "A12_90") (pintype "bidirectional"))
      (node (ref "Q1") (pin "2") (pinfunction "TR1_GATE_2") (pintype "bidirectional"))
      (node (ref "Q2") (pin "2") (pinfunction "TR1_GATE_2") (pintype "bidirectional"))
      (node (ref "R6") (pin "1") (pinfunction "1_1") (pintype "passive"))
    )
    (net (code "345") (name "/SDCARD_CD#") (class "Default")
      (node (ref "D7") (pin "1") (pinfunction "I/O_&_THERMAL_PAD_1") (pintype "bidirectional"))
      (node (ref "MICRO_SD_CARD_SLOT") (pin "DT") (pinfunction "DETECT_DT") (pintype "bidirectional"))
    )
    (net (code "346") (name "/SDCARD_CLK") (class "Default")
      (node (ref "D6") (pin "1") (pinfunction "I/O_&_THERMAL_PAD_1") (pintype "bidirectional"))
      (node (ref "MICRO_SD_CARD_SLOT") (pin "5") (pinfunction "CLK_5") (pintype "bidirectional"))
      (node (ref "R901") (pin "2") (pinfunction "2_2") (pintype "passive"))
    )
    (net (code "347") (name "/SDCARD_CMD") (class "Default")
      (node (ref "D4") (pin "1") (pinfunction "I/O_&_THERMAL_PAD_1") (pintype "bidirectional"))
      (node (ref "MICRO_SD_CARD_SLOT") (pin "3") (pinfunction "CMD_3") (pintype "bidirectional"))
      (node (ref "SDIO_LEVEL_SHIFTER") (pin "12") (pinfunction "CMDB1_12") (pintype "bidirectional"))
    )
    (net (code "348") (name "/SDCARD_D0") (class "Default")
      (node (ref "D9") (pin "1") (pinfunction "I/O_&_THERMAL_PAD_1") (pintype "bidirectional"))
      (node (ref "MICRO_SD_CARD_SLOT") (pin "7") (pinfunction "DAT0_7") (pintype "bidirectional"))
      (node (ref "SDIO_LEVEL_SHIFTER") (pin "14") (pinfunction "DAT0B1_14") (pintype "bidirectional"))
    )
    (net (code "349") (name "/SDCARD_D1") (class "Default")
      (node (ref "D8") (pin "1") (pinfunction "I/O_&_THERMAL_PAD_1") (pintype "bidirectional"))
      (node (ref "MICRO_SD_CARD_SLOT") (pin "8") (pinfunction "DAT1_8") (pintype "bidirectional"))
      (node (ref "SDIO_LEVEL_SHIFTER") (pin "15") (pinfunction "DAT1B1_15") (pintype "bidirectional"))
    )
    (net (code "350") (name "/SDCARD_D2") (class "Default")
      (node (ref "D2") (pin "1") (pinfunction "I/O_&_THERMAL_PAD_1") (pintype "bidirectional"))
      (node (ref "MICRO_SD_CARD_SLOT") (pin "1") (pinfunction "DATA2_1") (pintype "bidirectional"))
      (node (ref "SDIO_LEVEL_SHIFTER") (pin "8") (pinfunction "DAT2B1_8") (pintype "bidirectional"))
    )
    (net (code "351") (name "/SDCARD_D3") (class "Default")
      (node (ref "D3") (pin "1") (pinfunction "I/O_&_THERMAL_PAD_1") (pintype "bidirectional"))
      (node (ref "MICRO_SD_CARD_SLOT") (pin "2") (pinfunction "CD/DAT3_2") (pintype "bidirectional"))
      (node (ref "SDIO_LEVEL_SHIFTER") (pin "10") (pinfunction "DAT3B1_10") (pintype "bidirectional"))
    )
    (net (code "352") (name "/USBH_D_N") (class "Default")
      (node (ref "CONN_A") (pin "67") (pinfunction "A133_67") (pintype "bidirectional"))
    )
    (net (code "353") (name "/USBH_D_P") (class "Default")
      (node (ref "CONN_A") (pin "66") (pinfunction "A131_66") (pintype "bidirectional"))
      (node (ref "J1") (pin "1") (pinfunction "1_1") (pintype "bidirectional"))
    )
    (net (code "354") (name "/USB_CPEN") (class "Default")
      (node (ref "CONN_A") (pin "148") (pinfunction "A128_148") (pintype "bidirectional"))
    )
    (net (code "355") (name "/USB_D_N") (class "Default")
      (node (ref "CONN_A") (pin "65") (pinfunction "A129_65") (pintype "bidirectional"))
      (node (ref "IC1") (pin "6") (pinfunction "D1-_6") (pintype "bidirectional"))
      (node (ref "J1") (pin "2") (pinfunction "2_2") (pintype "bidirectional"))
    )
    (net (code "356") (name "/USB_D_P") (class "Default")
      (node (ref "CONN_A") (pin "64") (pinfunction "A127_64") (pintype "bidirectional"))
      (node (ref "IC1") (pin "1") (pinfunction "D1+_1") (pintype "bidirectional"))
      (node (ref "J1") (pin "3") (pinfunction "3_3") (pintype "bidirectional"))
    )
    (net (code "357") (name "/USB_SSRX_N") (class "Default")
      (node (ref "CONN_A") (pin "71") (pinfunction "A141_71") (pintype "bidirectional"))
    )
    (net (code "358") (name "/USB_SSRX_P") (class "Default")
      (node (ref "CONN_A") (pin "69") (pinfunction "A137_69") (pintype "bidirectional"))
    )
    (net (code "359") (name "/USB_SSTX_N") (class "Default")
      (node (ref "CONN_A") (pin "154") (pinfunction "A140_154") (pintype "bidirectional"))
    )
    (net (code "360") (name "/USB_SSTX_P") (class "Default")
      (node (ref "CONN_A") (pin "152") (pinfunction "A136_152") (pintype "bidirectional"))
    )
    (net (code "361") (name "/VBUS_DETECT") (class "Default")
      (node (ref "CONN_A") (pin "139") (pinfunction "A110_139") (pintype "bidirectional"))
    )
    (net (code "362") (name "/VCC_1V8") (class "Default")
      (node (ref "CONN_B") (pin "110") (pinfunction "A52_110") (pintype "bidirectional"))
      (node (ref "CONN_B") (pin "122") (pinfunction "A76_122") (pintype "bidirectional"))
      (node (ref "CONN_B") (pin "138") (pinfunction "A108_138") (pintype "bidirectional"))
      (node (ref "CONN_B") (pin "148") (pinfunction "A128_148") (pintype "bidirectional"))
      (node (ref "CONN_C") (pin "42") (pinfunction "A83_42") (pintype "bidirectional"))
      (node (ref "CONN_C") (pin "62") (pinfunction "A123_62") (pintype "bidirectional"))
      (node (ref "CONN_C") (pin "83") (pinfunction "A165_83") (pintype "bidirectional"))
    )
    (net (code "363") (name "/VCC_2V5") (class "Default")
      (node (ref "CONN_A") (pin "115") (pinfunction "A62_115") (pintype "bidirectional"))
      (node (ref "CONN_A") (pin "27") (pinfunction "A53_27") (pintype "bidirectional"))
      (node (ref "CONN_A") (pin "33") (pinfunction "A65_33") (pintype "bidirectional"))
      (node (ref "CONN_A") (pin "45") (pinfunction "A89_45") (pintype "bidirectional"))
    )
    (net (code "364") (name "/VCC_3V3") (class "Default")
      (node (ref "C1") (pin "1") (pinfunction "1_1") (pintype "passive"))
      (node (ref "CONN_A") (pin "109") (pinfunction "A50_109") (pintype "bidirectional"))
      (node (ref "CONN_A") (pin "127") (pinfunction "A86_127") (pintype "bidirectional"))
      (node (ref "CONN_A") (pin "15") (pinfunction "A29_15") (pintype "bidirectional"))
      (node (ref "CONN_A") (pin "97") (pinfunction "A26_97") (pintype "bidirectional"))
      (node (ref "CONN_A1") (pin "42") (pinfunction "A83_42") (pintype "bidirectional"))
      (node (ref "CONN_A1") (pin "43") (pinfunction "A85_43") (pintype "bidirectional"))
      (node (ref "CONN_A1") (pin "44") (pinfunction "A87_44") (pintype "bidirectional"))
      (node (ref "CONN_A1") (pin "45") (pinfunction "A89_45") (pintype "bidirectional"))
      (node (ref "CONN_A1") (pin "46") (pinfunction "A91_46") (pintype "bidirectional"))
      (node (ref "CONN_A1") (pin "47") (pinfunction "A93_47") (pintype "bidirectional"))
      (node (ref "CONN_A1") (pin "48") (pinfunction "A95_48") (pintype "bidirectional"))
      (node (ref "CONN_A1") (pin "49") (pinfunction "A97_49") (pintype "bidirectional"))
      (node (ref "CONN_A1") (pin "50") (pinfunction "A99_50") (pintype "bidirectional"))
      (node (ref "CONN_B") (pin "160") (pinfunction "A152_160") (pintype "bidirectional"))
      (node (ref "CONN_B") (pin "28") (pinfunction "A55_28") (pintype "bidirectional"))
      (node (ref "CONN_B") (pin "40") (pinfunction "A79_40") (pintype "bidirectional"))
      (node (ref "CONN_B") (pin "58") (pinfunction "A115_58") (pintype "bidirectional"))
      (node (ref "CONN_B") (pin "64") (pinfunction "A127_64") (pintype "bidirectional"))
      (node (ref "CONN_B") (pin "78") (pinfunction "A155_78") (pintype "bidirectional"))
      (node (ref "CONN_C") (pin "132") (pinfunction "A96_132") (pintype "bidirectional"))
      (node (ref "CONN_C") (pin "152") (pinfunction "A136_152") (pintype "bidirectional"))
      (node (ref "CONN_C") (pin "52") (pinfunction "A103_52") (pintype "bidirectional"))
      (node (ref "CONN_C") (pin "72") (pinfunction "A143_72") (pintype "bidirectional"))
      (node (ref "JTAG") (pin "2") (pinfunction "2_2") (pintype "passive"))
      (node (ref "MICRO_SD_CARD_SLOT") (pin "4") (pinfunction "VDD_4") (pintype "power_in"))
      (node (ref "R3") (pin "1") (pinfunction "1_1") (pintype "passive"))
      (node (ref "R4") (pin "1") (pinfunction "1_1") (pintype "passive"))
      (node (ref "SDIO_LEVEL_SHIFTER") (pin "17") (pinfunction "VCCB1_17") (pintype "bidirectional"))
    )
    (net (code "365") (name "/VCC_BAT") (class "Default")
      (node (ref "CONN_A") (pin "168") (pinfunction "A168_168") (pintype "bidirectional"))
    )
    (net (code "366") (name "/VCC_CFG_MIO") (class "Default")
      (node (ref "C10") (pin "1") (pinfunction "1_1") (pintype "passive"))
      (node (ref "C11") (pin "1") (pinfunction "1_1") (pintype "passive"))
      (node (ref "C9") (pin "1") (pinfunction "1_1") (pintype "passive"))
      (node (ref "CONN_A") (pin "121") (pinfunction "A74_121") (pintype "bidirectional"))
      (node (ref "IC4") (pin "2") (pinfunction "SUB_2") (pintype "bidirectional"))
      (node (ref "IC4") (pin "4") (pinfunction "VDD_4") (pintype "bidirectional"))
      (node (ref "SDIO_LEVEL_SHIFTER") (pin "24") (pinfunction "SEL_24") (pintype "bidirectional"))
      (node (ref "SDIO_LEVEL_SHIFTER") (pin "5") (pinfunction "VCCA_5") (pintype "bidirectional"))
      (node (ref "VCC_1") (pin "1") (pinfunction "1_1") (pintype "passive"))
    )
    (net (code "367") (name "/VCC_IO") (class "Default")
      (node (ref "C6") (pin "1") (pinfunction "1_1") (pintype "passive"))
      (node (ref "C7") (pin "1") (pinfunction "1_1") (pintype "passive"))
      (node (ref "C8") (pin "1") (pinfunction "1_1") (pintype "passive"))
      (node (ref "CONN_A") (pin "103") (pinfunction "A38_103") (pintype "bidirectional"))
      (node (ref "CONN_A1") (pin "32") (pinfunction "A63_32") (pintype "bidirectional"))
      (node (ref "CONN_A1") (pin "33") (pinfunction "A65_33") (pintype "bidirectional"))
      (node (ref "CONN_A1") (pin "34") (pinfunction "A67_34") (pintype "bidirectional"))
      (node (ref "CONN_A1") (pin "35") (pinfunction "A69_35") (pintype "bidirectional"))
      (node (ref "CONN_A1") (pin "36") (pinfunction "A71_36") (pintype "bidirectional"))
      (node (ref "CONN_A1") (pin "37") (pinfunction "A73_37") (pintype "bidirectional"))
      (node (ref "CONN_A1") (pin "38") (pinfunction "A75_38") (pintype "bidirectional"))
      (node (ref "CONN_A1") (pin "39") (pinfunction "A77_39") (pintype "bidirectional"))
      (node (ref "CONN_A1") (pin "40") (pinfunction "A79_40") (pintype "bidirectional"))
      (node (ref "CONN_A3") (pin "1") (pinfunction "A1_1") (pintype "bidirectional"))
      (node (ref "CONN_A3") (pin "2") (pinfunction "A3_2") (pintype "bidirectional"))
      (node (ref "CONN_A3") (pin "3") (pinfunction "A5_3") (pintype "bidirectional"))
      (node (ref "CONN_A3") (pin "4") (pinfunction "A7_4") (pintype "bidirectional"))
      (node (ref "CONN_A3") (pin "5") (pinfunction "A9_5") (pintype "bidirectional"))
      (node (ref "CONN_A3") (pin "6") (pinfunction "A11_6") (pintype "bidirectional"))
      (node (ref "CONN_A3") (pin "7") (pinfunction "A13_7") (pintype "bidirectional"))
      (node (ref "CONN_A3") (pin "85") (pinfunction "A2_85") (pintype "bidirectional"))
      (node (ref "CONN_A3") (pin "86") (pinfunction "A4_86") (pintype "bidirectional"))
      (node (ref "CONN_A3") (pin "87") (pinfunction "A6_87") (pintype "bidirectional"))
      (node (ref "CONN_A3") (pin "88") (pinfunction "A8_88") (pintype "bidirectional"))
      (node (ref "CONN_A3") (pin "89") (pinfunction "A10_89") (pintype "bidirectional"))
      (node (ref "CONN_A3") (pin "90") (pinfunction "A12_90") (pintype "bidirectional"))
      (node (ref "CONN_A3") (pin "91") (pinfunction "A14_91") (pintype "bidirectional"))
      (node (ref "CONN_B") (pin "116") (pinfunction "A64_116") (pintype "bidirectional"))
      (node (ref "CONN_B") (pin "128") (pinfunction "A88_128") (pintype "bidirectional"))
      (node (ref "CONN_B") (pin "154") (pinfunction "A140_154") (pintype "bidirectional"))
      (node (ref "CONN_B") (pin "34") (pinfunction "A67_34") (pintype "bidirectional"))
      (node (ref "CONN_C") (pin "122") (pinfunction "A76_122") (pintype "bidirectional"))
      (node (ref "CONN_C") (pin "142") (pinfunction "A116_142") (pintype "bidirectional"))
      (node (ref "CONN_C") (pin "163") (pinfunction "A158_163") (pintype "bidirectional"))
      (node (ref "VCC_2") (pin "1") (pinfunction "1_1") (pintype "passive"))
    )
    (net (code "368") (name "/VCC_IO_B47") (class "Default")
      (node (ref "Q3") (pin "5") (pinfunction "TR2_GATE_5") (pintype "bidirectional"))
    )
    (net (code "369") (name "/VCC_IO_B65") (class "Default")
      (node (ref "Q2") (pin "5") (pinfunction "TR2_GATE_5") (pintype "bidirectional"))
    )
    (net (code "370") (name "/VCC_IO_B66") (class "Default")
      (node (ref "CONN_B") (pin "48") (pinfunction "A95_48") (pintype "bidirectional"))
      (node (ref "CONN_B") (pin "72") (pinfunction "A143_72") (pintype "bidirectional"))
    )
    (net (code "371") (name "/VCC_MISC") (class "Default")
      (node (ref "CONN_A1") (pin "22") (pinfunction "A43_22") (pintype "bidirectional"))
      (node (ref "CONN_A1") (pin "23") (pinfunction "A45_23") (pintype "bidirectional"))
      (node (ref "CONN_A1") (pin "24") (pinfunction "A47_24") (pintype "bidirectional"))
      (node (ref "CONN_A1") (pin "25") (pinfunction "A49_25") (pintype "bidirectional"))
      (node (ref "CONN_A1") (pin "26") (pinfunction "A51_26") (pintype "bidirectional"))
      (node (ref "CONN_A1") (pin "27") (pinfunction "A53_27") (pintype "bidirectional"))
      (node (ref "CONN_A1") (pin "28") (pinfunction "A55_28") (pintype "bidirectional"))
      (node (ref "CONN_A1") (pin "29") (pinfunction "A57_29") (pintype "bidirectional"))
      (node (ref "CONN_A1") (pin "30") (pinfunction "A59_30") (pintype "bidirectional"))
    )
    (net (code "372") (name "/VCC_MOD") (class "Default")
      (node (ref "C3") (pin "1") (pinfunction "1_1") (pintype "passive"))
      (node (ref "C4") (pin "1") (pinfunction "1_1") (pintype "passive"))
      (node (ref "C5") (pin "1") (pinfunction "1_1") (pintype "passive"))
      (node (ref "CONN_A") (pin "1") (pinfunction "A1_1") (pintype "bidirectional"))
      (node (ref "CONN_A") (pin "2") (pinfunction "A3_2") (pintype "bidirectional"))
      (node (ref "CONN_A") (pin "3") (pinfunction "A5_3") (pintype "bidirectional"))
      (node (ref "CONN_A") (pin "4") (pinfunction "A7_4") (pintype "bidirectional"))
      (node (ref "CONN_A") (pin "5") (pinfunction "A9_5") (pintype "bidirectional"))
      (node (ref "CONN_A") (pin "6") (pinfunction "A11_6") (pintype "bidirectional"))
      (node (ref "CONN_A") (pin "85") (pinfunction "A2_85") (pintype "bidirectional"))
      (node (ref "CONN_A") (pin "86") (pinfunction "A4_86") (pintype "bidirectional"))
      (node (ref "CONN_A") (pin "87") (pinfunction "A6_87") (pintype "bidirectional"))
      (node (ref "CONN_A") (pin "88") (pinfunction "A8_88") (pintype "bidirectional"))
      (node (ref "CONN_A1") (pin "1") (pinfunction "A1_1") (pintype "bidirectional"))
      (node (ref "CONN_A1") (pin "10") (pinfunction "A19_10") (pintype "bidirectional"))
      (node (ref "CONN_A1") (pin "11") (pinfunction "A21_11") (pintype "bidirectional"))
      (node (ref "CONN_A1") (pin "12") (pinfunction "A23_12") (pintype "bidirectional"))
      (node (ref "CONN_A1") (pin "13") (pinfunction "A25_13") (pintype "bidirectional"))
      (node (ref "CONN_A1") (pin "14") (pinfunction "A27_14") (pintype "bidirectional"))
      (node (ref "CONN_A1") (pin "15") (pinfunction "A29_15") (pintype "bidirectional"))
      (node (ref "CONN_A1") (pin "16") (pinfunction "A31_16") (pintype "bidirectional"))
      (node (ref "CONN_A1") (pin "17") (pinfunction "A33_17") (pintype "bidirectional"))
      (node (ref "CONN_A1") (pin "18") (pinfunction "A35_18") (pintype "bidirectional"))
      (node (ref "CONN_A1") (pin "19") (pinfunction "A37_19") (pintype "bidirectional"))
      (node (ref "CONN_A1") (pin "2") (pinfunction "A3_2") (pintype "bidirectional"))
      (node (ref "CONN_A1") (pin "20") (pinfunction "A39_20") (pintype "bidirectional"))
      (node (ref "CONN_A1") (pin "3") (pinfunction "A5_3") (pintype "bidirectional"))
      (node (ref "CONN_A1") (pin "4") (pinfunction "A7_4") (pintype "bidirectional"))
      (node (ref "CONN_A1") (pin "5") (pinfunction "A9_5") (pintype "bidirectional"))
      (node (ref "CONN_A1") (pin "6") (pinfunction "A11_6") (pintype "bidirectional"))
      (node (ref "CONN_A1") (pin "7") (pinfunction "A13_7") (pintype "bidirectional"))
      (node (ref "CONN_A1") (pin "8") (pinfunction "A15_8") (pintype "bidirectional"))
      (node (ref "CONN_A1") (pin "9") (pinfunction "A17_9") (pintype "bidirectional"))
      (node (ref "CONN_A2") (pin "1") (pinfunction "A1_1") (pintype "bidirectional"))
      (node (ref "CONN_A2") (pin "2") (pinfunction "A3_2") (pintype "bidirectional"))
      (node (ref "CONN_A2") (pin "3") (pinfunction "A5_3") (pintype "bidirectional"))
      (node (ref "CONN_A2") (pin "4") (pinfunction "A7_4") (pintype "bidirectional"))
      (node (ref "CONN_A2") (pin "5") (pinfunction "A9_5") (pintype "bidirectional"))
      (node (ref "CONN_A2") (pin "85") (pinfunction "A2_85") (pintype "bidirectional"))
      (node (ref "CONN_A2") (pin "86") (pinfunction "A4_86") (pintype "bidirectional"))
      (node (ref "CONN_A2") (pin "87") (pinfunction "A6_87") (pintype "bidirectional"))
      (node (ref "CONN_A2") (pin "88") (pinfunction "A8_88") (pintype "bidirectional"))
      (node (ref "CONN_A2") (pin "89") (pinfunction "A10_89") (pintype "bidirectional"))
      (node (ref "R8") (pin "2") (pinfunction "2_2") (pintype "passive"))
      (node (ref "R9") (pin "1") (pinfunction "1_1") (pintype "passive"))
      (node (ref "VCC_5V") (pin "3") (pinfunction "3_3") (pintype "passive"))
    )
    (net (code "373") (name "/VMON_0V9") (class "Default")
      (node (ref "CONN_B") (pin "84") (pinfunction "A167_84") (pintype "bidirectional"))
    )
    (net (code "374") (name "/VMON_1V2_BAT") (class "Default")
      (node (ref "CONN_B") (pin "88") (pinfunction "A8_88") (pintype "bidirectional"))
    )
    (net (code "375") (name "/VMON_1V8") (class "Default")
      (node (ref "CONN_B") (pin "168") (pinfunction "A168_168") (pintype "bidirectional"))
    )
    (net (code "376") (name "/VMON_INT") (class "Default")
      (node (ref "CONN_A") (pin "135") (pinfunction "A102_135") (pintype "bidirectional"))
    )
    (net (code "377") (name "/VMON_PSINT") (class "Default")
      (node (ref "CONN_C") (pin "88") (pinfunction "A8_88") (pintype "bidirectional"))
    )
    (net (code "378") (name "GND") (class "Default")
      (node (ref "C1") (pin "2") (pinfunction "2_2") (pintype "passive"))
      (node (ref "C10") (pin "2") (pinfunction "2_2") (pintype "passive"))
      (node (ref "C11") (pin "2") (pinfunction "2_2") (pintype "passive"))
      (node (ref "C12") (pin "2") (pinfunction "2_2") (pintype "passive"))
      (node (ref "C13") (pin "2") (pinfunction "2_2") (pintype "passive"))
      (node (ref "C14") (pin "2") (pinfunction "2_2") (pintype "passive"))
      (node (ref "C2") (pin "2") (pinfunction "2_2") (pintype "passive"))
      (node (ref "C3") (pin "2") (pinfunction "2_2") (pintype "passive"))
      (node (ref "C4") (pin "2") (pinfunction "2_2") (pintype "passive"))
      (node (ref "C5") (pin "2") (pinfunction "2_2") (pintype "passive"))
      (node (ref "C6") (pin "2") (pinfunction "2_2") (pintype "passive"))
      (node (ref "C7") (pin "2") (pinfunction "2_2") (pintype "passive"))
      (node (ref "C8") (pin "2") (pinfunction "2_2") (pintype "passive"))
      (node (ref "C9") (pin "2") (pinfunction "2_2") (pintype "passive"))
      (node (ref "CONN1") (pin "2") (pinfunction "2_2") (pintype "passive"))
      (node (ref "CONN1") (pin "3") (pinfunction "2_3") (pintype "passive"))
      (node (ref "CONN1") (pin "4") (pinfunction "2_4") (pintype "passive"))
      (node (ref "CONN1") (pin "5") (pinfunction "2_5") (pintype "passive"))
      (node (ref "CONN2") (pin "2") (pinfunction "2_2") (pintype "passive"))
      (node (ref "CONN2") (pin "3") (pinfunction "2_3") (pintype "passive"))
      (node (ref "CONN2") (pin "4") (pinfunction "2_4") (pintype "passive"))
      (node (ref "CONN2") (pin "5") (pinfunction "2_5") (pintype "passive"))
      (node (ref "CONN3") (pin "2") (pinfunction "2_2") (pintype "passive"))
      (node (ref "CONN3") (pin "3") (pinfunction "2_3") (pintype "passive"))
      (node (ref "CONN3") (pin "4") (pinfunction "2_4") (pintype "passive"))
      (node (ref "CONN3") (pin "5") (pinfunction "2_5") (pintype "passive"))
      (node (ref "CONN_A") (pin "100") (pinfunction "A32_100") (pintype "bidirectional"))
      (node (ref "CONN_A") (pin "106") (pinfunction "A44_106") (pintype "bidirectional"))
      (node (ref "CONN_A") (pin "112") (pinfunction "A56_112") (pintype "bidirectional"))
      (node (ref "CONN_A") (pin "118") (pinfunction "A68_118") (pintype "bidirectional"))
      (node (ref "CONN_A") (pin "12") (pinfunction "A23_12") (pintype "bidirectional"))
      (node (ref "CONN_A") (pin "124") (pinfunction "A80_124") (pintype "bidirectional"))
      (node (ref "CONN_A") (pin "132") (pinfunction "A96_132") (pintype "bidirectional"))
      (node (ref "CONN_A") (pin "138") (pinfunction "A108_138") (pintype "bidirectional"))
      (node (ref "CONN_A") (pin "144") (pinfunction "A120_144") (pintype "bidirectional"))
      (node (ref "CONN_A") (pin "151") (pinfunction "A134_151") (pintype "bidirectional"))
      (node (ref "CONN_A") (pin "153") (pinfunction "A138_153") (pintype "bidirectional"))
      (node (ref "CONN_A") (pin "155") (pinfunction "A142_155") (pintype "bidirectional"))
      (node (ref "CONN_A") (pin "167") (pinfunction "A166_167") (pintype "bidirectional"))
      (node (ref "CONN_A") (pin "18") (pinfunction "A35_18") (pintype "bidirectional"))
      (node (ref "CONN_A") (pin "24") (pinfunction "A47_24") (pintype "bidirectional"))
      (node (ref "CONN_A") (pin "30") (pinfunction "A59_30") (pintype "bidirectional"))
      (node (ref "CONN_A") (pin "36") (pinfunction "A71_36") (pintype "bidirectional"))
      (node (ref "CONN_A") (pin "42") (pinfunction "A83_42") (pintype "bidirectional"))
      (node (ref "CONN_A") (pin "50") (pinfunction "A99_50") (pintype "bidirectional"))
      (node (ref "CONN_A") (pin "55") (pinfunction "A109_55") (pintype "bidirectional"))
      (node (ref "CONN_A") (pin "63") (pinfunction "A125_63") (pintype "bidirectional"))
      (node (ref "CONN_A") (pin "68") (pinfunction "A135_68") (pintype "bidirectional"))
      (node (ref "CONN_A") (pin "7") (pinfunction "A13_7") (pintype "bidirectional"))
      (node (ref "CONN_A") (pin "70") (pinfunction "A139_70") (pintype "bidirectional"))
      (node (ref "CONN_A") (pin "72") (pinfunction "A143_72") (pintype "bidirectional"))
      (node (ref "CONN_A") (pin "84") (pinfunction "A167_84") (pintype "bidirectional"))
      (node (ref "CONN_A") (pin "91") (pinfunction "A14_91") (pintype "bidirectional"))
      (node (ref "CONN_A") (pin "94") (pinfunction "A20_94") (pintype "bidirectional"))
      (node (ref "CONN_A1") (pin "127") (pinfunction "A86_127") (pintype "bidirectional"))
      (node (ref "CONN_A1") (pin "128") (pinfunction "A88_128") (pintype "bidirectional"))
      (node (ref "CONN_A1") (pin "131") (pinfunction "A94_131") (pintype "bidirectional"))
      (node (ref "CONN_A1") (pin "136") (pinfunction "A104_136") (pintype "bidirectional"))
      (node (ref "CONN_A1") (pin "141") (pinfunction "A114_141") (pintype "bidirectional"))
      (node (ref "CONN_A1") (pin "146") (pinfunction "A124_146") (pintype "bidirectional"))
      (node (ref "CONN_A1") (pin "151") (pinfunction "A134_151") (pintype "bidirectional"))
      (node (ref "CONN_A1") (pin "156") (pinfunction "A144_156") (pintype "bidirectional"))
      (node (ref "CONN_A1") (pin "163") (pinfunction "A158_163") (pintype "bidirectional"))
      (node (ref "CONN_A1") (pin "166") (pinfunction "A164_166") (pintype "bidirectional"))
      (node (ref "CONN_A1") (pin "21") (pinfunction "A41_21") (pintype "bidirectional"))
      (node (ref "CONN_A1") (pin "31") (pinfunction "A61_31") (pintype "bidirectional"))
      (node (ref "CONN_A1") (pin "41") (pinfunction "A81_41") (pintype "bidirectional"))
      (node (ref "CONN_A1") (pin "51") (pinfunction "A101_51") (pintype "bidirectional"))
      (node (ref "CONN_A1") (pin "52") (pinfunction "A103_52") (pintype "bidirectional"))
      (node (ref "CONN_A1") (pin "57") (pinfunction "A113_57") (pintype "bidirectional"))
      (node (ref "CONN_A1") (pin "62") (pinfunction "A123_62") (pintype "bidirectional"))
      (node (ref "CONN_A1") (pin "67") (pinfunction "A133_67") (pintype "bidirectional"))
      (node (ref "CONN_A1") (pin "72") (pinfunction "A143_72") (pintype "bidirectional"))
      (node (ref "CONN_A1") (pin "77") (pinfunction "A153_77") (pintype "bidirectional"))
      (node (ref "CONN_A1") (pin "82") (pinfunction "A163_82") (pintype "bidirectional"))
      (node (ref "CONN_A1") (pin "88") (pinfunction "A8_88") (pintype "bidirectional"))
      (node (ref "CONN_A1") (pin "92") (pinfunction "A16_92") (pintype "bidirectional"))
      (node (ref "CONN_A1") (pin "96") (pinfunction "A24_96") (pintype "bidirectional"))
      (node (ref "CONN_A2") (pin "101") (pinfunction "A34_101") (pintype "bidirectional"))
      (node (ref "CONN_A2") (pin "103") (pinfunction "A38_103") (pintype "bidirectional"))
      (node (ref "CONN_A2") (pin "105") (pinfunction "A42_105") (pintype "bidirectional"))
      (node (ref "CONN_A2") (pin "107") (pinfunction "A46_107") (pintype "bidirectional"))
      (node (ref "CONN_A2") (pin "109") (pinfunction "A50_109") (pintype "bidirectional"))
      (node (ref "CONN_A2") (pin "111") (pinfunction "A54_111") (pintype "bidirectional"))
      (node (ref "CONN_A2") (pin "113") (pinfunction "A58_113") (pintype "bidirectional"))
      (node (ref "CONN_A2") (pin "116") (pinfunction "A64_116") (pintype "bidirectional"))
      (node (ref "CONN_A2") (pin "119") (pinfunction "A70_119") (pintype "bidirectional"))
      (node (ref "CONN_A2") (pin "12") (pinfunction "A23_12") (pintype "bidirectional"))
      (node (ref "CONN_A2") (pin "122") (pinfunction "A76_122") (pintype "bidirectional"))
      (node (ref "CONN_A2") (pin "125") (pinfunction "A82_125") (pintype "bidirectional"))
      (node (ref "CONN_A2") (pin "132") (pinfunction "A96_132") (pintype "bidirectional"))
      (node (ref "CONN_A2") (pin "14") (pinfunction "A27_14") (pintype "bidirectional"))
      (node (ref "CONN_A2") (pin "141") (pinfunction "A114_141") (pintype "bidirectional"))
      (node (ref "CONN_A2") (pin "150") (pinfunction "A132_150") (pintype "bidirectional"))
      (node (ref "CONN_A2") (pin "159") (pinfunction "A150_159") (pintype "bidirectional"))
      (node (ref "CONN_A2") (pin "16") (pinfunction "A31_16") (pintype "bidirectional"))
      (node (ref "CONN_A2") (pin "162") (pinfunction "A156_162") (pintype "bidirectional"))
      (node (ref "CONN_A2") (pin "18") (pinfunction "A35_18") (pintype "bidirectional"))
      (node (ref "CONN_A2") (pin "20") (pinfunction "A39_20") (pintype "bidirectional"))
      (node (ref "CONN_A2") (pin "22") (pinfunction "A43_22") (pintype "bidirectional"))
      (node (ref "CONN_A2") (pin "24") (pinfunction "A47_24") (pintype "bidirectional"))
      (node (ref "CONN_A2") (pin "26") (pinfunction "A51_26") (pintype "bidirectional"))
      (node (ref "CONN_A2") (pin "28") (pinfunction "A55_28") (pintype "bidirectional"))
      (node (ref "CONN_A2") (pin "31") (pinfunction "A61_31") (pintype "bidirectional"))
      (node (ref "CONN_A2") (pin "34") (pinfunction "A67_34") (pintype "bidirectional"))
      (node (ref "CONN_A2") (pin "37") (pinfunction "A73_37") (pintype "bidirectional"))
      (node (ref "CONN_A2") (pin "40") (pinfunction "A79_40") (pintype "bidirectional"))
      (node (ref "CONN_A2") (pin "43") (pinfunction "A85_43") (pintype "bidirectional"))
      (node (ref "CONN_A2") (pin "52") (pinfunction "A103_52") (pintype "bidirectional"))
      (node (ref "CONN_A2") (pin "6") (pinfunction "A11_6") (pintype "bidirectional"))
      (node (ref "CONN_A2") (pin "61") (pinfunction "A121_61") (pintype "bidirectional"))
      (node (ref "CONN_A2") (pin "7") (pinfunction "A13_7") (pintype "bidirectional"))
      (node (ref "CONN_A2") (pin "70") (pinfunction "A139_70") (pintype "bidirectional"))
      (node (ref "CONN_A2") (pin "77") (pinfunction "A153_77") (pintype "bidirectional"))
      (node (ref "CONN_A2") (pin "80") (pinfunction "A159_80") (pintype "bidirectional"))
      (node (ref "CONN_A2") (pin "90") (pinfunction "A12_90") (pintype "bidirectional"))
      (node (ref "CONN_A2") (pin "91") (pinfunction "A14_91") (pintype "bidirectional"))
      (node (ref "CONN_A2") (pin "94") (pinfunction "A20_94") (pintype "bidirectional"))
      (node (ref "CONN_A2") (pin "97") (pinfunction "A26_97") (pintype "bidirectional"))
      (node (ref "CONN_A2") (pin "99") (pinfunction "A30_99") (pintype "bidirectional"))
      (node (ref "CONN_A3") (pin "101") (pinfunction "A34_101") (pintype "bidirectional"))
      (node (ref "CONN_A3") (pin "103") (pinfunction "A38_103") (pintype "bidirectional"))
      (node (ref "CONN_A3") (pin "105") (pinfunction "A42_105") (pintype "bidirectional"))
      (node (ref "CONN_A3") (pin "107") (pinfunction "A46_107") (pintype "bidirectional"))
      (node (ref "CONN_A3") (pin "109") (pinfunction "A50_109") (pintype "bidirectional"))
      (node (ref "CONN_A3") (pin "111") (pinfunction "A54_111") (pintype "bidirectional"))
      (node (ref "CONN_A3") (pin "113") (pinfunction "A58_113") (pintype "bidirectional"))
      (node (ref "CONN_A3") (pin "115") (pinfunction "A62_115") (pintype "bidirectional"))
      (node (ref "CONN_A3") (pin "118") (pinfunction "A68_118") (pintype "bidirectional"))
      (node (ref "CONN_A3") (pin "121") (pinfunction "A74_121") (pintype "bidirectional"))
      (node (ref "CONN_A3") (pin "126") (pinfunction "A84_126") (pintype "bidirectional"))
      (node (ref "CONN_A3") (pin "131") (pinfunction "A94_131") (pintype "bidirectional"))
      (node (ref "CONN_A3") (pin "138") (pinfunction "A108_138") (pintype "bidirectional"))
      (node (ref "CONN_A3") (pin "14") (pinfunction "A27_14") (pintype "bidirectional"))
      (node (ref "CONN_A3") (pin "147") (pinfunction "A126_147") (pintype "bidirectional"))
      (node (ref "CONN_A3") (pin "154") (pinfunction "A140_154") (pintype "bidirectional"))
      (node (ref "CONN_A3") (pin "159") (pinfunction "A150_159") (pintype "bidirectional"))
      (node (ref "CONN_A3") (pin "16") (pinfunction "A31_16") (pintype "bidirectional"))
      (node (ref "CONN_A3") (pin "164") (pinfunction "A160_164") (pintype "bidirectional"))
      (node (ref "CONN_A3") (pin "18") (pinfunction "A35_18") (pintype "bidirectional"))
      (node (ref "CONN_A3") (pin "20") (pinfunction "A39_20") (pintype "bidirectional"))
      (node (ref "CONN_A3") (pin "22") (pinfunction "A43_22") (pintype "bidirectional"))
      (node (ref "CONN_A3") (pin "24") (pinfunction "A47_24") (pintype "bidirectional"))
      (node (ref "CONN_A3") (pin "26") (pinfunction "A51_26") (pintype "bidirectional"))
      (node (ref "CONN_A3") (pin "28") (pinfunction "A55_28") (pintype "bidirectional"))
      (node (ref "CONN_A3") (pin "30") (pinfunction "A59_30") (pintype "bidirectional"))
      (node (ref "CONN_A3") (pin "33") (pinfunction "A65_33") (pintype "bidirectional"))
      (node (ref "CONN_A3") (pin "36") (pinfunction "A71_36") (pintype "bidirectional"))
      (node (ref "CONN_A3") (pin "39") (pinfunction "A77_39") (pintype "bidirectional"))
      (node (ref "CONN_A3") (pin "44") (pinfunction "A87_44") (pintype "bidirectional"))
      (node (ref "CONN_A3") (pin "49") (pinfunction "A97_49") (pintype "bidirectional"))
      (node (ref "CONN_A3") (pin "58") (pinfunction "A115_58") (pintype "bidirectional"))
      (node (ref "CONN_A3") (pin "65") (pinfunction "A129_65") (pintype "bidirectional"))
      (node (ref "CONN_A3") (pin "72") (pinfunction "A143_72") (pintype "bidirectional"))
      (node (ref "CONN_A3") (pin "77") (pinfunction "A153_77") (pintype "bidirectional"))
      (node (ref "CONN_A3") (pin "8") (pinfunction "A15_8") (pintype "bidirectional"))
      (node (ref "CONN_A3") (pin "82") (pinfunction "A163_82") (pintype "bidirectional"))
      (node (ref "CONN_A3") (pin "9") (pinfunction "A17_9") (pintype "bidirectional"))
      (node (ref "CONN_A3") (pin "92") (pinfunction "A16_92") (pintype "bidirectional"))
      (node (ref "CONN_A3") (pin "93") (pinfunction "A18_93") (pintype "bidirectional"))
      (node (ref "CONN_A3") (pin "96") (pinfunction "A24_96") (pintype "bidirectional"))
      (node (ref "CONN_A3") (pin "99") (pinfunction "A30_99") (pintype "bidirectional"))
      (node (ref "CONN_B") (pin "1") (pinfunction "A1_1") (pintype "bidirectional"))
      (node (ref "CONN_B") (pin "10") (pinfunction "A19_10") (pintype "bidirectional"))
      (node (ref "CONN_B") (pin "101") (pinfunction "A34_101") (pintype "bidirectional"))
      (node (ref "CONN_B") (pin "103") (pinfunction "A38_103") (pintype "bidirectional"))
      (node (ref "CONN_B") (pin "105") (pinfunction "A42_105") (pintype "bidirectional"))
      (node (ref "CONN_B") (pin "107") (pinfunction "A46_107") (pintype "bidirectional"))
      (node (ref "CONN_B") (pin "113") (pinfunction "A58_113") (pintype "bidirectional"))
      (node (ref "CONN_B") (pin "119") (pinfunction "A70_119") (pintype "bidirectional"))
      (node (ref "CONN_B") (pin "12") (pinfunction "A23_12") (pintype "bidirectional"))
      (node (ref "CONN_B") (pin "125") (pinfunction "A82_125") (pintype "bidirectional"))
      (node (ref "CONN_B") (pin "133") (pinfunction "A98_133") (pintype "bidirectional"))
      (node (ref "CONN_B") (pin "14") (pinfunction "A27_14") (pintype "bidirectional"))
      (node (ref "CONN_B") (pin "143") (pinfunction "A118_143") (pintype "bidirectional"))
      (node (ref "CONN_B") (pin "151") (pinfunction "A134_151") (pintype "bidirectional"))
      (node (ref "CONN_B") (pin "157") (pinfunction "A146_157") (pintype "bidirectional"))
      (node (ref "CONN_B") (pin "16") (pinfunction "A31_16") (pintype "bidirectional"))
      (node (ref "CONN_B") (pin "163") (pinfunction "A158_163") (pintype "bidirectional"))
      (node (ref "CONN_B") (pin "18") (pinfunction "A35_18") (pintype "bidirectional"))
      (node (ref "CONN_B") (pin "20") (pinfunction "A39_20") (pintype "bidirectional"))
      (node (ref "CONN_B") (pin "22") (pinfunction "A43_22") (pintype "bidirectional"))
      (node (ref "CONN_B") (pin "25") (pinfunction "A49_25") (pintype "bidirectional"))
      (node (ref "CONN_B") (pin "31") (pinfunction "A61_31") (pintype "bidirectional"))
      (node (ref "CONN_B") (pin "37") (pinfunction "A73_37") (pintype "bidirectional"))
      (node (ref "CONN_B") (pin "43") (pinfunction "A85_43") (pintype "bidirectional"))
      (node (ref "CONN_B") (pin "53") (pinfunction "A105_53") (pintype "bidirectional"))
      (node (ref "CONN_B") (pin "6") (pinfunction "A11_6") (pintype "bidirectional"))
      (node (ref "CONN_B") (pin "61") (pinfunction "A121_61") (pintype "bidirectional"))
      (node (ref "CONN_B") (pin "69") (pinfunction "A137_69") (pintype "bidirectional"))
      (node (ref "CONN_B") (pin "75") (pinfunction "A149_75") (pintype "bidirectional"))
      (node (ref "CONN_B") (pin "8") (pinfunction "A15_8") (pintype "bidirectional"))
      (node (ref "CONN_B") (pin "81") (pinfunction "A161_81") (pintype "bidirectional"))
      (node (ref "CONN_B") (pin "85") (pinfunction "A2_85") (pintype "bidirectional"))
      (node (ref "CONN_B") (pin "91") (pinfunction "A14_91") (pintype "bidirectional"))
      (node (ref "CONN_B") (pin "93") (pinfunction "A18_93") (pintype "bidirectional"))
      (node (ref "CONN_B") (pin "95") (pinfunction "A22_95") (pintype "bidirectional"))
      (node (ref "CONN_B") (pin "97") (pinfunction "A26_97") (pintype "bidirectional"))
      (node (ref "CONN_B") (pin "99") (pinfunction "A30_99") (pintype "bidirectional"))
      (node (ref "CONN_C") (pin "1") (pinfunction "A1_1") (pintype "bidirectional"))
      (node (ref "CONN_C") (pin "10") (pinfunction "A19_10") (pintype "bidirectional"))
      (node (ref "CONN_C") (pin "101") (pinfunction "A34_101") (pintype "bidirectional"))
      (node (ref "CONN_C") (pin "103") (pinfunction "A38_103") (pintype "bidirectional"))
      (node (ref "CONN_C") (pin "105") (pinfunction "A42_105") (pintype "bidirectional"))
      (node (ref "CONN_C") (pin "107") (pinfunction "A46_107") (pintype "bidirectional"))
      (node (ref "CONN_C") (pin "110") (pinfunction "A52_110") (pintype "bidirectional"))
      (node (ref "CONN_C") (pin "113") (pinfunction "A58_113") (pintype "bidirectional"))
      (node (ref "CONN_C") (pin "116") (pinfunction "A64_116") (pintype "bidirectional"))
      (node (ref "CONN_C") (pin "119") (pinfunction "A70_119") (pintype "bidirectional"))
      (node (ref "CONN_C") (pin "12") (pinfunction "A23_12") (pintype "bidirectional"))
      (node (ref "CONN_C") (pin "127") (pinfunction "A86_127") (pintype "bidirectional"))
      (node (ref "CONN_C") (pin "137") (pinfunction "A106_137") (pintype "bidirectional"))
      (node (ref "CONN_C") (pin "14") (pinfunction "A27_14") (pintype "bidirectional"))
      (node (ref "CONN_C") (pin "147") (pinfunction "A126_147") (pintype "bidirectional"))
      (node (ref "CONN_C") (pin "157") (pinfunction "A146_157") (pintype "bidirectional"))
      (node (ref "CONN_C") (pin "16") (pinfunction "A31_16") (pintype "bidirectional"))
      (node (ref "CONN_C") (pin "160") (pinfunction "A152_160") (pintype "bidirectional"))
      (node (ref "CONN_C") (pin "168") (pinfunction "A168_168") (pintype "bidirectional"))
      (node (ref "CONN_C") (pin "18") (pinfunction "A35_18") (pintype "bidirectional"))
      (node (ref "CONN_C") (pin "20") (pinfunction "A39_20") (pintype "bidirectional"))
      (node (ref "CONN_C") (pin "22") (pinfunction "A43_22") (pintype "bidirectional"))
      (node (ref "CONN_C") (pin "25") (pinfunction "A49_25") (pintype "bidirectional"))
      (node (ref "CONN_C") (pin "28") (pinfunction "A55_28") (pintype "bidirectional"))
      (node (ref "CONN_C") (pin "31") (pinfunction "A61_31") (pintype "bidirectional"))
      (node (ref "CONN_C") (pin "34") (pinfunction "A67_34") (pintype "bidirectional"))
      (node (ref "CONN_C") (pin "37") (pinfunction "A73_37") (pintype "bidirectional"))
      (node (ref "CONN_C") (pin "47") (pinfunction "A93_47") (pintype "bidirectional"))
      (node (ref "CONN_C") (pin "57") (pinfunction "A113_57") (pintype "bidirectional"))
      (node (ref "CONN_C") (pin "6") (pinfunction "A11_6") (pintype "bidirectional"))
      (node (ref "CONN_C") (pin "67") (pinfunction "A133_67") (pintype "bidirectional"))
      (node (ref "CONN_C") (pin "75") (pinfunction "A149_75") (pintype "bidirectional"))
      (node (ref "CONN_C") (pin "78") (pinfunction "A155_78") (pintype "bidirectional"))
      (node (ref "CONN_C") (pin "8") (pinfunction "A15_8") (pintype "bidirectional"))
      (node (ref "CONN_C") (pin "84") (pinfunction "A167_84") (pintype "bidirectional"))
      (node (ref "CONN_C") (pin "85") (pinfunction "A2_85") (pintype "bidirectional"))
      (node (ref "CONN_C") (pin "91") (pinfunction "A14_91") (pintype "bidirectional"))
      (node (ref "CONN_C") (pin "93") (pinfunction "A18_93") (pintype "bidirectional"))
      (node (ref "CONN_C") (pin "95") (pinfunction "A22_95") (pintype "bidirectional"))
      (node (ref "CONN_C") (pin "97") (pinfunction "A26_97") (pintype "bidirectional"))
      (node (ref "CONN_C") (pin "99") (pinfunction "A30_99") (pintype "bidirectional"))
      (node (ref "D2") (pin "2") (pinfunction "I/O_2") (pintype "bidirectional"))
      (node (ref "D3") (pin "2") (pinfunction "I/O_2") (pintype "bidirectional"))
      (node (ref "D4") (pin "2") (pinfunction "I/O_2") (pintype "bidirectional"))
      (node (ref "D6") (pin "2") (pinfunction "I/O_2") (pintype "bidirectional"))
      (node (ref "D7") (pin "2") (pinfunction "I/O_2") (pintype "bidirectional"))
      (node (ref "D8") (pin "2") (pinfunction "I/O_2") (pintype "bidirectional"))
      (node (ref "D9") (pin "2") (pinfunction "I/O_2") (pintype "bidirectional"))
      (node (ref "IC1") (pin "2") (pinfunction "GND_2") (pintype "power_in"))
      (node (ref "IC1") (pin "3") (pinfunction "D2+_3") (pintype "bidirectional"))
      (node (ref "IC1") (pin "4") (pinfunction "D2-_4") (pintype "bidirectional"))
      (node (ref "IC2") (pin "2") (pinfunction "GND_2") (pintype "power_in"))
      (node (ref "IC2") (pin "4") (pinfunction "D2-_4") (pintype "bidirectional"))
      (node (ref "IC2") (pin "6") (pinfunction "D1-_6") (pintype "bidirectional"))
      (node (ref "IC3") (pin "2") (pinfunction "GND_2") (pintype "power_in"))
      (node (ref "IC3") (pin "4") (pinfunction "D2-_4") (pintype "bidirectional"))
      (node (ref "IC3") (pin "6") (pinfunction "D1-_6") (pintype "bidirectional"))
      (node (ref "IC4") (pin "5") (pinfunction "GND_5") (pintype "bidirectional"))
      (node (ref "J1") (pin "4") (pinfunction "4_4") (pintype "bidirectional"))
      (node (ref "JP1") (pin "2") (pinfunction "2_2") (pintype "passive"))
      (node (ref "JTAG") (pin "1") (pinfunction "1_1") (pintype "passive"))
      (node (ref "JTAG") (pin "11") (pinfunction "11_11") (pintype "passive"))
      (node (ref "JTAG") (pin "13") (pinfunction "13_13") (pintype "passive"))
      (node (ref "JTAG") (pin "3") (pinfunction "3_3") (pintype "passive"))
      (node (ref "JTAG") (pin "5") (pinfunction "5_5") (pintype "passive"))
      (node (ref "JTAG") (pin "7") (pinfunction "7_7") (pintype "passive"))
      (node (ref "JTAG") (pin "9") (pinfunction "9_9") (pintype "passive"))
      (node (ref "MICRO_SD_CARD_SLOT") (pin "6") (pinfunction "VSS_6") (pintype "power_in"))
      (node (ref "MICRO_SD_CARD_SLOT") (pin "P1") (pinfunction "SHIELD_P1") (pintype "passive"))
      (node (ref "MICRO_SD_CARD_SLOT") (pin "P2") (pinfunction "SHIELD_P2") (pintype "passive"))
      (node (ref "MICRO_SD_CARD_SLOT") (pin "P3") (pinfunction "SHIELD_P3") (pintype "passive"))
      (node (ref "MICRO_SD_CARD_SLOT") (pin "P4") (pinfunction "SHIELD_P4") (pintype "passive"))
      (node (ref "MICRO_SD_CARD_SLOT") (pin "P5") (pinfunction "SHIELD_P5") (pintype "passive"))
      (node (ref "MICRO_SD_CARD_SLOT") (pin "SW") (pinfunction "SWITCH_SW") (pintype "bidirectional"))
      (node (ref "Q1") (pin "1") (pinfunction "TR1_SOURCE_1") (pintype "bidirectional"))
      (node (ref "Q1") (pin "4") (pinfunction "TR2_SOURCE_4") (pintype "bidirectional"))
      (node (ref "Q2") (pin "1") (pinfunction "TR1_SOURCE_1") (pintype "bidirectional"))
      (node (ref "Q3") (pin "1") (pinfunction "TR1_SOURCE_1") (pintype "bidirectional"))
      (node (ref "R10") (pin "1") (pinfunction "1_1") (pintype "passive"))
      (node (ref "R2") (pin "1") (pinfunction "1_1") (pintype "passive"))
      (node (ref "SDIO_LEVEL_SHIFTER") (pin "11") (pinfunction "GND_2_11") (pintype "bidirectional"))
      (node (ref "SDIO_LEVEL_SHIFTER") (pin "2") (pinfunction "GND_1_2") (pintype "bidirectional"))
      (node (ref "SDIO_LEVEL_SHIFTER") (pin "25") (pinfunction "THERMAL_PAD_25") (pintype "bidirectional"))
      (node (ref "SW1") (pin "P$2") (pinfunction "P$2_P$2") (pintype "passive"))
      (node (ref "SW2") (pin "P$2") (pinfunction "P$2_P$2") (pintype "passive"))
      (node (ref "VCC_1") (pin "2") (pinfunction "2_2") (pintype "passive"))
      (node (ref "VCC_1") (pin "3") (pinfunction "2_3") (pintype "passive"))
      (node (ref "VCC_1") (pin "4") (pinfunction "2_4") (pintype "passive"))
      (node (ref "VCC_1") (pin "5") (pinfunction "2_5") (pintype "passive"))
      (node (ref "VCC_2") (pin "2") (pinfunction "2_2") (pintype "passive"))
      (node (ref "VCC_2") (pin "3") (pinfunction "2_3") (pintype "passive"))
      (node (ref "VCC_2") (pin "4") (pinfunction "2_4") (pintype "passive"))
      (node (ref "VCC_2") (pin "5") (pinfunction "2_5") (pintype "passive"))
      (node (ref "VCC_5V") (pin "2") (pinfunction "2_2") (pintype "passive"))
    )
    (net (code "379") (name "Net-(D1-A)") (class "Default")
      (node (ref "C13") (pin "1") (pinfunction "1_1") (pintype "passive"))
      (node (ref "D1") (pin "2") (pinfunction "A_2") (pintype "bidirectional"))
      (node (ref "Q1") (pin "5") (pinfunction "TR2_GATE_5") (pintype "bidirectional"))
      (node (ref "Q1") (pin "6") (pinfunction "TR1_DRAIN_6") (pintype "bidirectional"))
      (node (ref "R10") (pin "2") (pinfunction "2_2") (pintype "passive"))
      (node (ref "R8") (pin "1") (pinfunction "1_1") (pintype "passive"))
    )
    (net (code "380") (name "Net-(IC4-CT)") (class "Default")
      (node (ref "C14") (pin "1") (pinfunction "1_1") (pintype "passive"))
      (node (ref "IC4") (pin "3") (pinfunction "CT_3") (pintype "bidirectional"))
    )
    (net (code "381") (name "Net-(IC4-VOUT)") (class "Default")
      (node (ref "IC4") (pin "1") (pinfunction "VOUT_1") (pintype "bidirectional"))
      (node (ref "R5") (pin "1") (pinfunction "1_1") (pintype "passive"))
    )
    (net (code "382") (name "Net-(JP1-Pad1)") (class "Default")
      (node (ref "JP1") (pin "1") (pinfunction "1_1") (pintype "passive"))
      (node (ref "R1") (pin "2") (pinfunction "2_2") (pintype "passive"))
    )
    (net (code "383") (name "Net-(JTAG-Pad4)") (class "Default")
      (node (ref "JTAG") (pin "4") (pinfunction "4_4") (pintype "passive"))
      (node (ref "RN1") (pin "1") (pinfunction "1_1") (pintype "passive"))
    )
    (net (code "384") (name "Net-(LED1-PadA)") (class "Default")
      (node (ref "LED1") (pin "A") (pinfunction "A_A") (pintype "passive"))
      (node (ref "R3") (pin "2") (pinfunction "2_2") (pintype "passive"))
    )
    (net (code "385") (name "Net-(LED2-PadA)") (class "Default")
      (node (ref "LED2") (pin "A") (pinfunction "A_A") (pintype "passive"))
      (node (ref "R4") (pin "2") (pinfunction "2_2") (pintype "passive"))
    )
    (net (code "386") (name "Net-(LED3-PadA)") (class "Default")
      (node (ref "LED3") (pin "A") (pinfunction "A_A") (pintype "passive"))
      (node (ref "R9") (pin "2") (pinfunction "2_2") (pintype "passive"))
    )
    (net (code "387") (name "Net-(Q1-TR2_DRAIN)") (class "Default")
      (node (ref "LED3") (pin "C") (pinfunction "C_C") (pintype "passive"))
      (node (ref "Q1") (pin "3") (pinfunction "TR2_DRAIN_3") (pintype "bidirectional"))
    )
    (net (code "388") (name "Net-(Q2-TR1_DRAIN)") (class "Default")
      (node (ref "Q2") (pin "4") (pinfunction "TR2_SOURCE_4") (pintype "bidirectional"))
      (node (ref "Q2") (pin "6") (pinfunction "TR1_DRAIN_6") (pintype "bidirectional"))
    )
    (net (code "389") (name "Net-(Q2-TR2_DRAIN)") (class "Default")
      (node (ref "Q2") (pin "3") (pinfunction "TR2_DRAIN_3") (pintype "bidirectional"))
      (node (ref "Q3") (pin "4") (pinfunction "TR2_SOURCE_4") (pintype "bidirectional"))
    )
    (net (code "390") (name "Net-(Q3-TR1_DRAIN)") (class "Default")
      (node (ref "LED1") (pin "C") (pinfunction "C_C") (pintype "passive"))
      (node (ref "Q3") (pin "6") (pinfunction "TR1_DRAIN_6") (pintype "bidirectional"))
    )
    (net (code "391") (name "Net-(Q3-TR2_DRAIN)") (class "Default")
      (node (ref "LED2") (pin "C") (pinfunction "C_C") (pintype "passive"))
      (node (ref "Q3") (pin "3") (pinfunction "TR2_DRAIN_3") (pintype "bidirectional"))
    )
    (net (code "392") (name "Net-(RN1B-1)") (class "Default")
      (node (ref "JTAG") (pin "6") (pinfunction "6_6") (pintype "passive"))
      (node (ref "RN1") (pin "2") (pinfunction "1_2") (pintype "passive"))
    )
    (net (code "393") (name "Net-(RN1C-1)") (class "Default")
      (node (ref "JTAG") (pin "8") (pinfunction "8_8") (pintype "passive"))
      (node (ref "RN1") (pin "3") (pinfunction "1_3") (pintype "passive"))
    )
    (net (code "394") (name "Net-(RN1D-1)") (class "Default")
      (node (ref "JTAG") (pin "10") (pinfunction "10_10") (pintype "passive"))
      (node (ref "RN1") (pin "4") (pinfunction "1_4") (pintype "passive"))
    )
    (net (code "395") (name "Net-(SDIO_LEVEL_SHIFTER-CLKB1)") (class "Default")
      (node (ref "R901") (pin "1") (pinfunction "1_1") (pintype "passive"))
      (node (ref "SDIO_LEVEL_SHIFTER") (pin "13") (pinfunction "CLKB1_13") (pintype "bidirectional"))
    )
    (net (code "396") (name "unconnected-(CONN_A1-A26-Pad97)") (class "Default")
      (node (ref "CONN_A1") (pin "97") (pinfunction "A26_97") (pintype "bidirectional"))
    )
    (net (code "397") (name "unconnected-(CONN_A1-A28-Pad98)") (class "Default")
      (node (ref "CONN_A1") (pin "98") (pinfunction "A28_98") (pintype "bidirectional"))
    )
    (net (code "398") (name "unconnected-(CONN_A1-A30-Pad99)") (class "Default")
      (node (ref "CONN_A1") (pin "99") (pinfunction "A30_99") (pintype "bidirectional"))
    )
    (net (code "399") (name "unconnected-(CONN_A1-A32-Pad100)") (class "Default")
      (node (ref "CONN_A1") (pin "100") (pinfunction "A32_100") (pintype "bidirectional"))
    )
    (net (code "400") (name "unconnected-(CONN_A1-A34-Pad101)") (class "Default")
      (node (ref "CONN_A1") (pin "101") (pinfunction "A34_101") (pintype "bidirectional"))
    )
    (net (code "401") (name "unconnected-(CONN_A1-A36-Pad102)") (class "Default")
      (node (ref "CONN_A1") (pin "102") (pinfunction "A36_102") (pintype "bidirectional"))
    )
    (net (code "402") (name "unconnected-(CONN_A1-A38-Pad103)") (class "Default")
      (node (ref "CONN_A1") (pin "103") (pinfunction "A38_103") (pintype "bidirectional"))
    )
    (net (code "403") (name "unconnected-(CONN_A1-A40-Pad104)") (class "Default")
      (node (ref "CONN_A1") (pin "104") (pinfunction "A40_104") (pintype "bidirectional"))
    )
    (net (code "404") (name "unconnected-(CONN_A1-A42-Pad105)") (class "Default")
      (node (ref "CONN_A1") (pin "105") (pinfunction "A42_105") (pintype "bidirectional"))
    )
    (net (code "405") (name "unconnected-(CONN_A1-A44-Pad106)") (class "Default")
      (node (ref "CONN_A1") (pin "106") (pinfunction "A44_106") (pintype "bidirectional"))
    )
    (net (code "406") (name "unconnected-(CONN_A1-A46-Pad107)") (class "Default")
      (node (ref "CONN_A1") (pin "107") (pinfunction "A46_107") (pintype "bidirectional"))
    )
    (net (code "407") (name "unconnected-(CONN_A1-A48-Pad108)") (class "Default")
      (node (ref "CONN_A1") (pin "108") (pinfunction "A48_108") (pintype "bidirectional"))
    )
    (net (code "408") (name "unconnected-(CONN_A1-A50-Pad109)") (class "Default")
      (node (ref "CONN_A1") (pin "109") (pinfunction "A50_109") (pintype "bidirectional"))
    )
    (net (code "409") (name "unconnected-(CONN_A1-A52-Pad110)") (class "Default")
      (node (ref "CONN_A1") (pin "110") (pinfunction "A52_110") (pintype "bidirectional"))
    )
    (net (code "410") (name "unconnected-(CONN_A1-A54-Pad111)") (class "Default")
      (node (ref "CONN_A1") (pin "111") (pinfunction "A54_111") (pintype "bidirectional"))
    )
    (net (code "411") (name "unconnected-(CONN_A1-A56-Pad112)") (class "Default")
      (node (ref "CONN_A1") (pin "112") (pinfunction "A56_112") (pintype "bidirectional"))
    )
    (net (code "412") (name "unconnected-(CONN_A1-A58-Pad113)") (class "Default")
      (node (ref "CONN_A1") (pin "113") (pinfunction "A58_113") (pintype "bidirectional"))
    )
    (net (code "413") (name "unconnected-(CONN_A1-A60-Pad114)") (class "Default")
      (node (ref "CONN_A1") (pin "114") (pinfunction "A60_114") (pintype "bidirectional"))
    )
    (net (code "414") (name "unconnected-(CONN_A1-A62-Pad115)") (class "Default")
      (node (ref "CONN_A1") (pin "115") (pinfunction "A62_115") (pintype "bidirectional"))
    )
    (net (code "415") (name "unconnected-(CONN_A1-A64-Pad116)") (class "Default")
      (node (ref "CONN_A1") (pin "116") (pinfunction "A64_116") (pintype "bidirectional"))
    )
    (net (code "416") (name "unconnected-(CONN_A1-A66-Pad117)") (class "Default")
      (node (ref "CONN_A1") (pin "117") (pinfunction "A66_117") (pintype "bidirectional"))
    )
    (net (code "417") (name "unconnected-(CONN_A1-A68-Pad118)") (class "Default")
      (node (ref "CONN_A1") (pin "118") (pinfunction "A68_118") (pintype "bidirectional"))
    )
    (net (code "418") (name "unconnected-(CONN_A1-A70-Pad119)") (class "Default")
      (node (ref "CONN_A1") (pin "119") (pinfunction "A70_119") (pintype "bidirectional"))
    )
    (net (code "419") (name "unconnected-(CONN_A1-A72-Pad120)") (class "Default")
      (node (ref "CONN_A1") (pin "120") (pinfunction "A72_120") (pintype "bidirectional"))
    )
    (net (code "420") (name "unconnected-(CONN_A1-A74-Pad121)") (class "Default")
      (node (ref "CONN_A1") (pin "121") (pinfunction "A74_121") (pintype "bidirectional"))
    )
    (net (code "421") (name "unconnected-(CONN_A1-A76-Pad122)") (class "Default")
      (node (ref "CONN_A1") (pin "122") (pinfunction "A76_122") (pintype "bidirectional"))
    )
    (net (code "422") (name "unconnected-(CONN_A1-A78-Pad123)") (class "Default")
      (node (ref "CONN_A1") (pin "123") (pinfunction "A78_123") (pintype "bidirectional"))
    )
    (net (code "423") (name "unconnected-(CONN_A1-A80-Pad124)") (class "Default")
      (node (ref "CONN_A1") (pin "124") (pinfunction "A80_124") (pintype "bidirectional"))
    )
    (net (code "424") (name "unconnected-(CONN_A1-A82-Pad125)") (class "Default")
      (node (ref "CONN_A1") (pin "125") (pinfunction "A82_125") (pintype "bidirectional"))
    )
    (net (code "425") (name "unconnected-(CONN_A1-A84-Pad126)") (class "Default")
      (node (ref "CONN_A1") (pin "126") (pinfunction "A84_126") (pintype "bidirectional"))
    )
    (net (code "426") (name "unconnected-(IC1-NC-Pad5)") (class "Default")
      (node (ref "IC1") (pin "5") (pinfunction "NC_5") (pintype "no_connect"))
    )
    (net (code "427") (name "unconnected-(IC2-NC-Pad5)") (class "Default")
      (node (ref "IC2") (pin "5") (pinfunction "NC_5") (pintype "no_connect"))
    )
    (net (code "428") (name "unconnected-(IC3-NC-Pad5)") (class "Default")
      (node (ref "IC3") (pin "5") (pinfunction "NC_5") (pintype "no_connect"))
    )
    (net (code "429") (name "unconnected-(JTAG-Pad12)") (class "Default")
      (node (ref "JTAG") (pin "12") (pinfunction "12_12") (pintype "passive"))
    )
    (net (code "430") (name "unconnected-(SDIO_LEVEL_SHIFTER-CLKB0-Pad19)") (class "Default")
      (node (ref "SDIO_LEVEL_SHIFTER") (pin "19") (pinfunction "CLKB0_19") (pintype "bidirectional"))
    )
    (net (code "431") (name "unconnected-(SDIO_LEVEL_SHIFTER-CMDB0-Pad20)") (class "Default")
      (node (ref "SDIO_LEVEL_SHIFTER") (pin "20") (pinfunction "CMDB0_20") (pintype "bidirectional"))
    )
    (net (code "432") (name "unconnected-(SDIO_LEVEL_SHIFTER-DA0B0-Pad18)") (class "Default")
      (node (ref "SDIO_LEVEL_SHIFTER") (pin "18") (pinfunction "DA0B0_18") (pintype "bidirectional"))
    )
    (net (code "433") (name "unconnected-(SDIO_LEVEL_SHIFTER-DAT1B0-Pad16)") (class "Default")
      (node (ref "SDIO_LEVEL_SHIFTER") (pin "16") (pinfunction "DAT1B0_16") (pintype "bidirectional"))
    )
    (net (code "434") (name "unconnected-(SDIO_LEVEL_SHIFTER-DAT2B0-Pad23)") (class "Default")
      (node (ref "SDIO_LEVEL_SHIFTER") (pin "23") (pinfunction "DAT2B0_23") (pintype "bidirectional"))
    )
    (net (code "435") (name "unconnected-(SDIO_LEVEL_SHIFTER-DAT3B0-Pad22)") (class "Default")
      (node (ref "SDIO_LEVEL_SHIFTER") (pin "22") (pinfunction "DAT3B0_22") (pintype "bidirectional"))
    )
    (net (code "436") (name "unconnected-(SDIO_LEVEL_SHIFTER-VCCB0-Pad21)") (class "Default")
      (node (ref "SDIO_LEVEL_SHIFTER") (pin "21") (pinfunction "VCCB0_21") (pintype "bidirectional"))
    )
    (net (code "437") (name "unconnected-(VCC_5V-Pad1)") (class "Default")
      (node (ref "VCC_5V") (pin "1") (pinfunction "1_1") (pintype "passive"))
    )
  )
)
